# DBBC7205S.net
KiCad netlist of a schematic drawn in Altium Designer
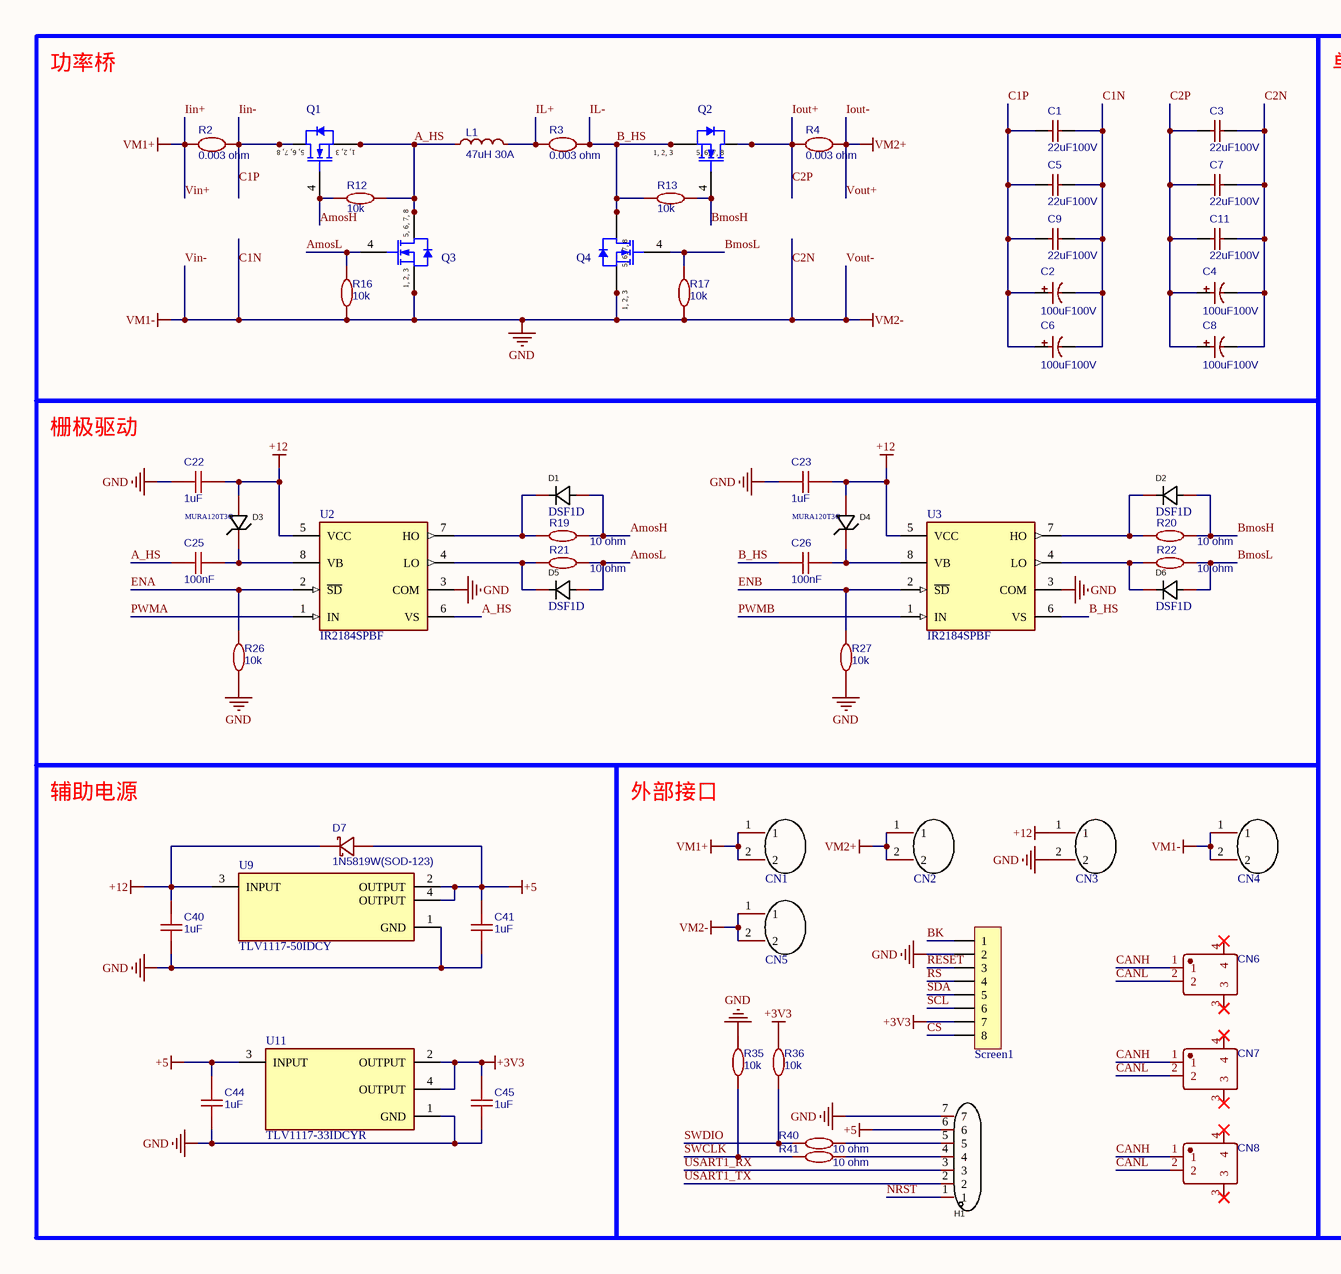
[diagram p0: DBBC7205S.SchDoc, left]
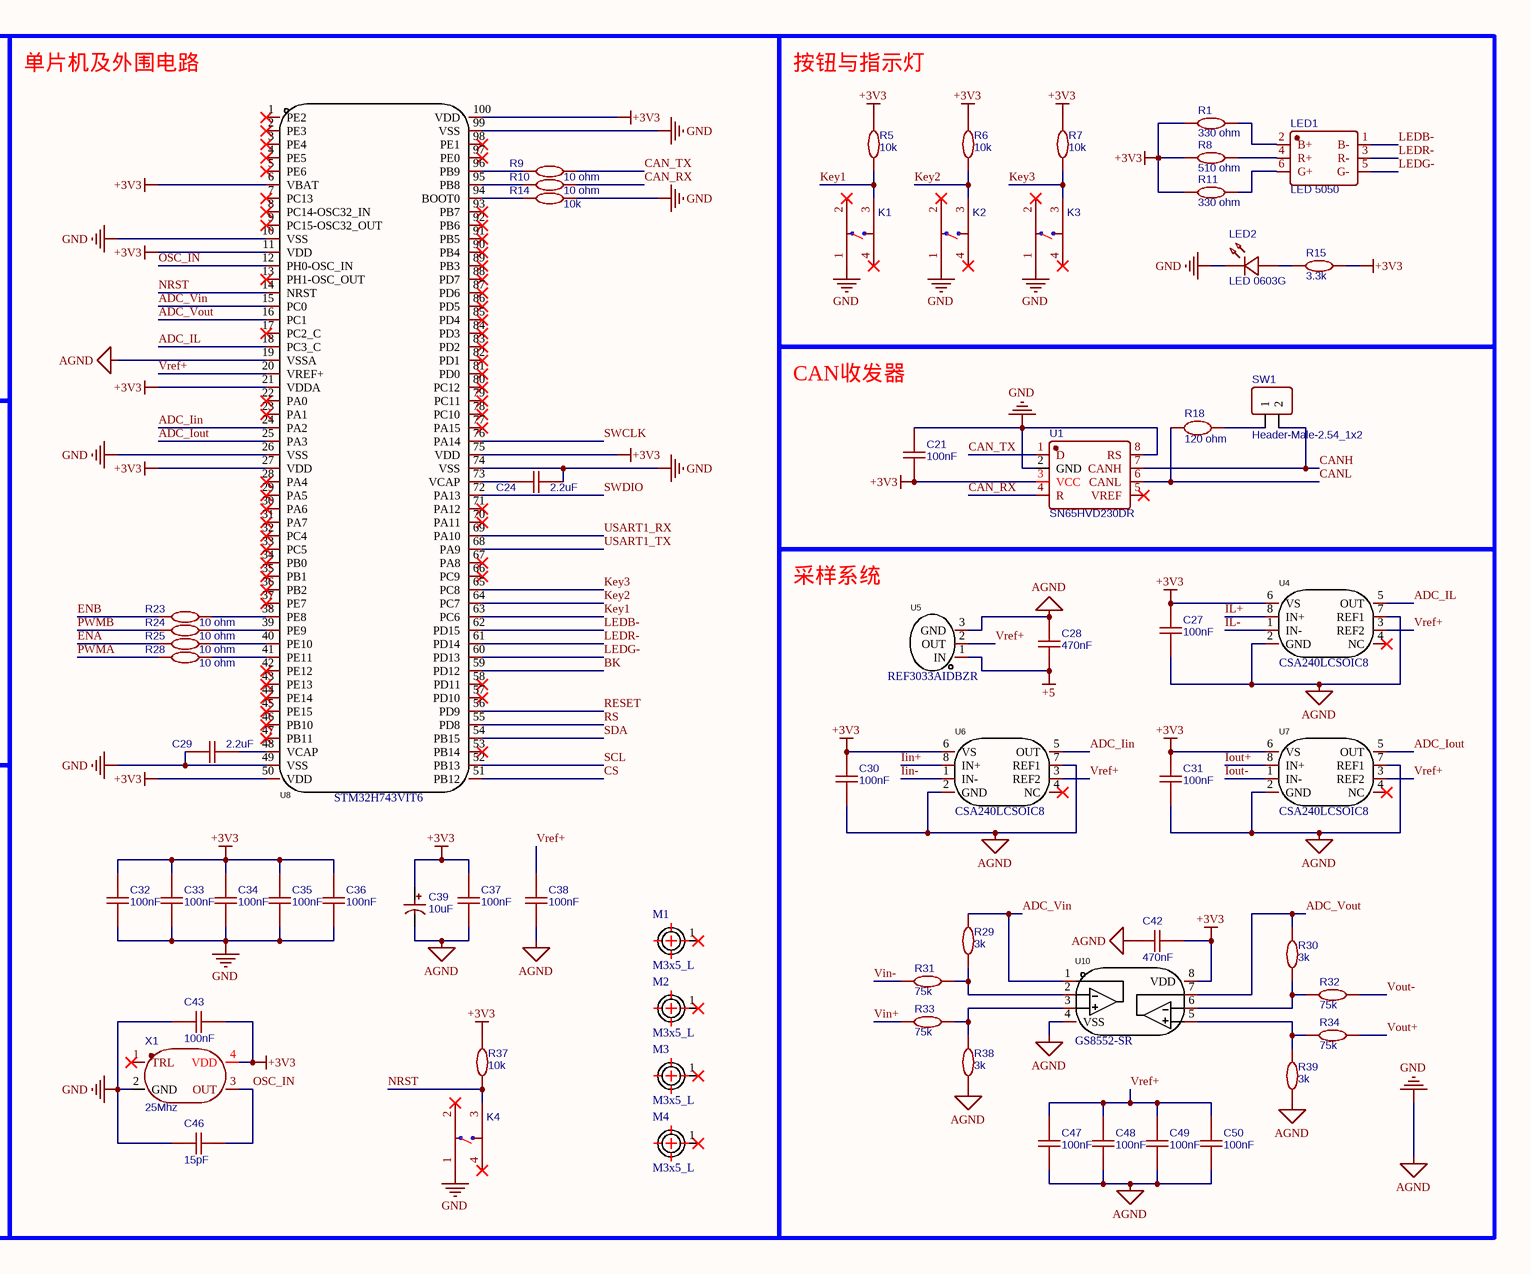
[diagram p1: DBBC7205S.SchDoc, right]

(export (version "E")
  (design (tool "Eeschema 10.0.6"))
  (components
    (comp (ref "C1")
      (value "22uF100V")
      (footprint "C1206")
      (fields
        (field (name "BOM_MANUFACTURER PART") "1206B102K202NT")
        (field (name "BOM_SUPPLIER PART") "C9196")
      )
      (libsource (lib "RC_schlib") (part "C1206"))
    )
    (comp (ref "C2")
      (value "100uF100V")
      (footprint "CAP 5.0*10*16")
      (description "脚距5mm直径10mm高度16mm")
      (fields
        (field (name "BOM_MANUFACTURER PART") "50V 100uF 8X12")
        (field (name "BOM_SUPPLIER PART") "C2749")
      )
      (libsource (lib "eCap_schlib") (part "CAP 5.0*10*16"))
    )
    (comp (ref "C3")
      (value "22uF100V")
      (footprint "C1206")
      (fields
        (field (name "BOM_MANUFACTURER PART") "1206B102K202NT")
        (field (name "BOM_SUPPLIER PART") "C9196")
      )
      (libsource (lib "RC_schlib") (part "C1206"))
    )
    (comp (ref "C4")
      (value "100uF100V")
      (footprint "CAP 5.0*10*16")
      (description "脚距5mm直径10mm高度16mm")
      (fields
        (field (name "BOM_MANUFACTURER PART") "50V 100uF 8X12")
        (field (name "BOM_SUPPLIER PART") "C2749")
      )
      (libsource (lib "eCap_schlib") (part "CAP 5.0*10*16"))
    )
    (comp (ref "C5")
      (value "22uF100V")
      (footprint "C1206")
      (fields
        (field (name "BOM_MANUFACTURER PART") "1206B102K202NT")
        (field (name "BOM_SUPPLIER PART") "C9196")
      )
      (libsource (lib "RC_schlib") (part "C1206"))
    )
    (comp (ref "C6")
      (value "100uF100V")
      (footprint "CAP 5.0*10*16")
      (description "脚距5mm直径10mm高度16mm")
      (fields
        (field (name "BOM_MANUFACTURER PART") "50V 100uF 8X12")
        (field (name "BOM_SUPPLIER PART") "C2749")
      )
      (libsource (lib "eCap_schlib") (part "CAP 5.0*10*16"))
    )
    (comp (ref "C7")
      (value "22uF100V")
      (footprint "C1206")
      (fields
        (field (name "BOM_MANUFACTURER PART") "1206B102K202NT")
        (field (name "BOM_SUPPLIER PART") "C9196")
      )
      (libsource (lib "RC_schlib") (part "C1206"))
    )
    (comp (ref "C8")
      (value "100uF100V")
      (footprint "CAP 5.0*10*16")
      (description "脚距5mm直径10mm高度16mm")
      (fields
        (field (name "BOM_MANUFACTURER PART") "50V 100uF 8X12")
        (field (name "BOM_SUPPLIER PART") "C2749")
      )
      (libsource (lib "eCap_schlib") (part "CAP 5.0*10*16"))
    )
    (comp (ref "C9")
      (value "22uF100V")
      (footprint "C1206")
      (fields
        (field (name "BOM_MANUFACTURER PART") "1206B102K202NT")
        (field (name "BOM_SUPPLIER PART") "C9196")
      )
      (libsource (lib "RC_schlib") (part "C1206"))
    )
    (comp (ref "C11")
      (value "22uF100V")
      (footprint "C1206")
      (fields
        (field (name "BOM_MANUFACTURER PART") "1206B102K202NT")
        (field (name "BOM_SUPPLIER PART") "C9196")
      )
      (libsource (lib "RC_schlib") (part "C1206"))
    )
    (comp (ref "C21")
      (value "100nF")
      (footprint "C0603")
      (fields
        (field (name "BOM_MANUFACTURER PART") "CC0603KRX7R9BB104")
        (field (name "BOM_SUPPLIER PART") "C14663")
      )
      (libsource (lib "RC_schlib") (part "C0603"))
    )
    (comp (ref "C22")
      (value "1uF")
      (footprint "C0603")
      (fields
        (field (name "BOM_MANUFACTURER PART") "CC0603KRX7R9BB104")
        (field (name "BOM_SUPPLIER PART") "C14663")
      )
      (libsource (lib "RC_schlib") (part "C0603"))
    )
    (comp (ref "C23")
      (value "1uF")
      (footprint "C0603")
      (fields
        (field (name "BOM_MANUFACTURER PART") "CC0603KRX7R9BB104")
        (field (name "BOM_SUPPLIER PART") "C14663")
      )
      (libsource (lib "RC_schlib") (part "C0603"))
    )
    (comp (ref "C24")
      (value "2.2uF")
      (footprint "C0603")
      (fields
        (field (name "BOM_MANUFACTURER PART") "CC0603KRX7R9BB104")
        (field (name "BOM_SUPPLIER PART") "C14663")
      )
      (libsource (lib "RC_schlib") (part "C0603"))
    )
    (comp (ref "C25")
      (value "100nF")
      (footprint "C0603")
      (fields
        (field (name "BOM_MANUFACTURER PART") "CC0603KRX7R9BB104")
        (field (name "BOM_SUPPLIER PART") "C14663")
      )
      (libsource (lib "RC_schlib") (part "C0603"))
    )
    (comp (ref "C26")
      (value "100nF")
      (footprint "C0603")
      (fields
        (field (name "BOM_MANUFACTURER PART") "CC0603KRX7R9BB104")
        (field (name "BOM_SUPPLIER PART") "C14663")
      )
      (libsource (lib "RC_schlib") (part "C0603"))
    )
    (comp (ref "C27")
      (value "100nF")
      (footprint "C0603")
      (fields
        (field (name "BOM_MANUFACTURER PART") "CC0603KRX7R9BB104")
        (field (name "BOM_SUPPLIER PART") "C14663")
      )
      (libsource (lib "RC_schlib") (part "C0603"))
    )
    (comp (ref "C28")
      (value "470nF")
      (footprint "C0603")
      (fields
        (field (name "BOM_MANUFACTURER PART") "CC0603KRX7R9BB104")
        (field (name "BOM_SUPPLIER PART") "C14663")
      )
      (libsource (lib "RC_schlib") (part "C0603"))
    )
    (comp (ref "C29")
      (value "2.2uF")
      (footprint "C0603")
      (fields
        (field (name "BOM_MANUFACTURER PART") "CC0603KRX7R9BB104")
        (field (name "BOM_SUPPLIER PART") "C14663")
      )
      (libsource (lib "RC_schlib") (part "C0603"))
    )
    (comp (ref "C30")
      (value "100nF")
      (footprint "C0603")
      (fields
        (field (name "BOM_MANUFACTURER PART") "CC0603KRX7R9BB104")
        (field (name "BOM_SUPPLIER PART") "C14663")
      )
      (libsource (lib "RC_schlib") (part "C0603"))
    )
    (comp (ref "C31")
      (value "100nF")
      (footprint "C0603")
      (fields
        (field (name "BOM_MANUFACTURER PART") "CC0603KRX7R9BB104")
        (field (name "BOM_SUPPLIER PART") "C14663")
      )
      (libsource (lib "RC_schlib") (part "C0603"))
    )
    (comp (ref "C32")
      (value "100nF")
      (footprint "C0603")
      (fields
        (field (name "BOM_MANUFACTURER PART") "CC0603KRX7R9BB104")
        (field (name "BOM_SUPPLIER PART") "C14663")
      )
      (libsource (lib "RC_schlib") (part "C0603"))
    )
    (comp (ref "C33")
      (value "100nF")
      (footprint "C0603")
      (fields
        (field (name "BOM_MANUFACTURER PART") "CC0603KRX7R9BB104")
        (field (name "BOM_SUPPLIER PART") "C14663")
      )
      (libsource (lib "RC_schlib") (part "C0603"))
    )
    (comp (ref "C34")
      (value "100nF")
      (footprint "C0603")
      (fields
        (field (name "BOM_MANUFACTURER PART") "CC0603KRX7R9BB104")
        (field (name "BOM_SUPPLIER PART") "C14663")
      )
      (libsource (lib "RC_schlib") (part "C0603"))
    )
    (comp (ref "C35")
      (value "100nF")
      (footprint "C0603")
      (fields
        (field (name "BOM_MANUFACTURER PART") "CC0603KRX7R9BB104")
        (field (name "BOM_SUPPLIER PART") "C14663")
      )
      (libsource (lib "RC_schlib") (part "C0603"))
    )
    (comp (ref "C36")
      (value "100nF")
      (footprint "C0603")
      (fields
        (field (name "BOM_MANUFACTURER PART") "CC0603KRX7R9BB104")
        (field (name "BOM_SUPPLIER PART") "C14663")
      )
      (libsource (lib "RC_schlib") (part "C0603"))
    )
    (comp (ref "C37")
      (value "100nF")
      (footprint "C0603")
      (fields
        (field (name "BOM_MANUFACTURER PART") "CC0603KRX7R9BB104")
        (field (name "BOM_SUPPLIER PART") "C14663")
      )
      (libsource (lib "RC_schlib") (part "C0603"))
    )
    (comp (ref "C38")
      (value "100nF")
      (footprint "C0603")
      (fields
        (field (name "BOM_MANUFACTURER PART") "CC0603KRX7R9BB104")
        (field (name "BOM_SUPPLIER PART") "C14663")
      )
      (libsource (lib "RC_schlib") (part "C0603"))
    )
    (comp (ref "C39")
      (value "10uF")
      (footprint "CD A(3216)")
      (description "长3.2mm，宽1.6mm，厚1.6mm")
      (fields
        (field (name "BOM_MANUFACTURER PART") "50V 100uF 8X12")
        (field (name "BOM_SUPPLIER PART") "C2749")
      )
      (libsource (lib "eCap_schlib") (part "A型钽电容"))
    )
    (comp (ref "C40")
      (value "1uF")
      (footprint "C0603")
      (fields
        (field (name "BOM_MANUFACTURER PART") "CC0603KRX7R9BB104")
        (field (name "BOM_SUPPLIER PART") "C14663")
      )
      (libsource (lib "RC_schlib") (part "C0603"))
    )
    (comp (ref "C41")
      (value "1uF")
      (footprint "C0603")
      (fields
        (field (name "BOM_MANUFACTURER PART") "CC0603KRX7R9BB104")
        (field (name "BOM_SUPPLIER PART") "C14663")
      )
      (libsource (lib "RC_schlib") (part "C0603"))
    )
    (comp (ref "C42")
      (value "470nF")
      (footprint "C0603")
      (fields
        (field (name "BOM_MANUFACTURER PART") "CC0603KRX7R9BB104")
        (field (name "BOM_SUPPLIER PART") "C14663")
      )
      (libsource (lib "RC_schlib") (part "C0603"))
    )
    (comp (ref "C43")
      (value "100nF")
      (footprint "C0603")
      (fields
        (field (name "BOM_MANUFACTURER PART") "CC0603KRX7R9BB104")
        (field (name "BOM_SUPPLIER PART") "C14663")
      )
      (libsource (lib "RC_schlib") (part "C0603"))
    )
    (comp (ref "C44")
      (value "1uF")
      (footprint "C0603")
      (fields
        (field (name "BOM_MANUFACTURER PART") "CC0603KRX7R9BB104")
        (field (name "BOM_SUPPLIER PART") "C14663")
      )
      (libsource (lib "RC_schlib") (part "C0603"))
    )
    (comp (ref "C45")
      (value "1uF")
      (footprint "C0603")
      (fields
        (field (name "BOM_MANUFACTURER PART") "CC0603KRX7R9BB104")
        (field (name "BOM_SUPPLIER PART") "C14663")
      )
      (libsource (lib "RC_schlib") (part "C0603"))
    )
    (comp (ref "C46")
      (value "15pF")
      (footprint "C0603")
      (fields
        (field (name "BOM_MANUFACTURER PART") "CC0603KRX7R9BB104")
        (field (name "BOM_SUPPLIER PART") "C14663")
      )
      (libsource (lib "RC_schlib") (part "C0603"))
    )
    (comp (ref "C47")
      (value "100nF")
      (footprint "C0603")
      (fields
        (field (name "BOM_MANUFACTURER PART") "CC0603KRX7R9BB104")
        (field (name "BOM_SUPPLIER PART") "C14663")
      )
      (libsource (lib "RC_schlib") (part "C0603"))
    )
    (comp (ref "C48")
      (value "100nF")
      (footprint "C0603")
      (fields
        (field (name "BOM_MANUFACTURER PART") "CC0603KRX7R9BB104")
        (field (name "BOM_SUPPLIER PART") "C14663")
      )
      (libsource (lib "RC_schlib") (part "C0603"))
    )
    (comp (ref "C49")
      (value "100nF")
      (footprint "C0603")
      (fields
        (field (name "BOM_MANUFACTURER PART") "CC0603KRX7R9BB104")
        (field (name "BOM_SUPPLIER PART") "C14663")
      )
      (libsource (lib "RC_schlib") (part "C0603"))
    )
    (comp (ref "C50")
      (value "100nF")
      (footprint "C0603")
      (fields
        (field (name "BOM_MANUFACTURER PART") "CC0603KRX7R9BB104")
        (field (name "BOM_SUPPLIER PART") "C14663")
      )
      (libsource (lib "RC_schlib") (part "C0603"))
    )
    (comp (ref "CN1")
      (value "1729128")
      (footprint "CONN-TH_2P-P5.08")
      (description "间距:5.08mm;排数:1;每排PIN数:2;安装方式:直针;额定电流:13.5A;额定电压:400V;工作温度范围:-;颜色:绿色;")
      (fields (field (name "MANUFACTURER") "Phoenix Contact(菲尼克斯)"))
      (libsource (lib "MKDSN") (part "MKDSN5.08-2P"))
    )
    (comp (ref "CN2")
      (value "1729128")
      (footprint "CONN-TH_2P-P5.08")
      (description "间距:5.08mm;排数:1;每排PIN数:2;安装方式:直针;额定电流:13.5A;额定电压:400V;工作温度范围:-;颜色:绿色;")
      (fields (field (name "MANUFACTURER") "Phoenix Contact(菲尼克斯)"))
      (libsource (lib "MKDSN") (part "MKDSN5.08-2P"))
    )
    (comp (ref "CN3")
      (value "1729128")
      (footprint "CONN-TH_2P-P5.08")
      (description "间距:5.08mm;排数:1;每排PIN数:2;安装方式:直针;额定电流:13.5A;额定电压:400V;工作温度范围:-;颜色:绿色;")
      (fields (field (name "MANUFACTURER") "Phoenix Contact(菲尼克斯)"))
      (libsource (lib "MKDSN") (part "MKDSN5.08-2P"))
    )
    (comp (ref "CN4")
      (value "1729128")
      (footprint "CONN-TH_2P-P5.08")
      (description "间距:5.08mm;排数:1;每排PIN数:2;安装方式:直针;额定电流:13.5A;额定电压:400V;工作温度范围:-;颜色:绿色;")
      (fields (field (name "MANUFACTURER") "Phoenix Contact(菲尼克斯)"))
      (libsource (lib "MKDSN") (part "MKDSN5.08-2P"))
    )
    (comp (ref "CN5")
      (value "1729128")
      (footprint "CONN-TH_2P-P5.08")
      (description "间距:5.08mm;排数:1;每排PIN数:2;安装方式:直针;额定电流:13.5A;额定电压:400V;工作温度范围:-;颜色:绿色;")
      (fields (field (name "MANUFACTURER") "Phoenix Contact(菲尼克斯)"))
      (libsource (lib "MKDSN") (part "MKDSN5.08-2P"))
    )
    (comp (ref "CN6")
      (value "A1257WR-S-2P")
      (footprint "CONN-SMD_A1257WR-S-2P")
      (fields
        (field (name "BOM_SUPPLIER PART") "C225118")
        (field (name "BOM_MANUFACTURER PART") "A1257WV-S-2P")
        (field (name "CONTRIBUTOR") "LCSC")
      )
      (libsource (lib "GH1.25_schlib") (part "A1257WR-S-2P"))
    )
    (comp (ref "CN7")
      (value "A1257WR-S-2P")
      (footprint "CONN-SMD_A1257WR-S-2P")
      (fields
        (field (name "BOM_SUPPLIER PART") "C225118")
        (field (name "BOM_MANUFACTURER PART") "A1257WV-S-2P")
        (field (name "CONTRIBUTOR") "LCSC")
      )
      (libsource (lib "GH1.25_schlib") (part "A1257WR-S-2P"))
    )
    (comp (ref "CN8")
      (value "A1257WR-S-2P")
      (footprint "CONN-SMD_A1257WR-S-2P")
      (fields
        (field (name "BOM_SUPPLIER PART") "C225118")
        (field (name "BOM_MANUFACTURER PART") "A1257WV-S-2P")
        (field (name "CONTRIBUTOR") "LCSC")
      )
      (libsource (lib "GH1.25_schlib") (part "A1257WR-S-2P"))
    )
    (comp (ref "D1")
      (value "DSF1D")
      (footprint "SOD-123_L2.8-W1.8-LS3.7-RD")
      (description "小封装快恢复二极管")
      (fields (field (name "MANUFACTURER") "FUXINSEMI(富芯森美)"))
      (libsource (lib "Diode_schlib") (part "DSF1D"))
    )
    (comp (ref "D2")
      (value "DSF1D")
      (footprint "SOD-123_L2.8-W1.8-LS3.7-RD")
      (description "小封装快恢复二极管")
      (fields (field (name "MANUFACTURER") "FUXINSEMI(富芯森美)"))
      (libsource (lib "Diode_schlib") (part "DSF1D"))
    )
    (comp (ref "D3")
      (value "MURA120T3G")
      (footprint "SMA")
      (description "25ns 0.875V压降 1A快恢复二极管")
      (fields (field (name "MANUFACTURER") "MDD") (field (name "MANUFACTURER PART") "ES1J"))
      (libsource (lib "Diode_schlib") (part "MURA120T3G"))
    )
    (comp (ref "D4")
      (value "MURA120T3G")
      (footprint "SMA")
      (description "25ns 0.875V压降 1A快恢复二极管")
      (fields (field (name "MANUFACTURER") "MDD") (field (name "MANUFACTURER PART") "ES1J"))
      (libsource (lib "Diode_schlib") (part "MURA120T3G"))
    )
    (comp (ref "D5")
      (value "DSF1D")
      (footprint "SOD-123_L2.8-W1.8-LS3.7-RD")
      (description "小封装快恢复二极管")
      (fields (field (name "MANUFACTURER") "FUXINSEMI(富芯森美)"))
      (libsource (lib "Diode_schlib") (part "DSF1D"))
    )
    (comp (ref "D6")
      (value "DSF1D")
      (footprint "SOD-123_L2.8-W1.8-LS3.7-RD")
      (description "小封装快恢复二极管")
      (fields (field (name "MANUFACTURER") "FUXINSEMI(富芯森美)"))
      (libsource (lib "Diode_schlib") (part "DSF1D"))
    )
    (comp (ref "D7")
      (value "1N5819W(SOD-123)")
      (footprint "SOD-123")
      (fields
        (field (name "BOM_SUPPLIER PART") "C2931787")
        (field (name "BOM_MANUFACTURER PART") "SS34")
        (field (name "CONTRIBUTOR") "LCSC")
      )
      (libsource (lib "Diode_schlib") (part "1N5819W(SOD-123)"))
    )
    (comp (ref "H1")
      (value "7P卧贴排母")
      (footprint "HDR-SMD_7P-P2.54-H-F-L11.5")
      (fields
        (field (name "MANUFACTURER") "XKB Connectivity(中国星坤)")
        (field (name "MANUFACTURER PART") "X6511FRS-07-C85D30")
      )
      (libsource (lib "2.54CN_schlib") (part "7P卧贴排母"))
    )
    (comp (ref "K1")
      (value "TSW SMD-6*6*5")
      (footprint "TSW SMD-6*6*5")
      (fields
        (field (name "BOM_SUPPLIER PART") "C231715")
        (field (name "BOM_MANUFACTURER PART") "KAN0661-1001B")
        (field (name "CONTRIBUTOR") "LCSC")
      )
      (libsource (lib "Button_schlib") (part "TSW SMD-6*6*5"))
    )
    (comp (ref "K2")
      (value "TSW SMD-6*6*5")
      (footprint "TSW SMD-6*6*5")
      (fields
        (field (name "BOM_SUPPLIER PART") "C231715")
        (field (name "BOM_MANUFACTURER PART") "KAN0661-1001B")
        (field (name "CONTRIBUTOR") "LCSC")
      )
      (libsource (lib "Button_schlib") (part "TSW SMD-6*6*5"))
    )
    (comp (ref "K3")
      (value "TSW SMD-6*6*5")
      (footprint "TSW SMD-6*6*5")
      (fields
        (field (name "BOM_SUPPLIER PART") "C231715")
        (field (name "BOM_MANUFACTURER PART") "KAN0661-1001B")
        (field (name "CONTRIBUTOR") "LCSC")
      )
      (libsource (lib "Button_schlib") (part "TSW SMD-6*6*5"))
    )
    (comp (ref "K4")
      (value "TSW SMD-6*6*5")
      (footprint "TSW SMD-6*6*5")
      (fields
        (field (name "BOM_SUPPLIER PART") "C231715")
        (field (name "BOM_MANUFACTURER PART") "KAN0661-1001B")
        (field (name "CONTRIBUTOR") "LCSC")
      )
      (libsource (lib "Button_schlib") (part "TSW SMD-6*6*5"))
    )
    (comp (ref "L1")
      (value "47uH 30A")
      (footprint "106-125卧式")
      (fields
        (field (name "BOM_SUPPLIER PART") "C2936653")
        (field (name "BOM_MANUFACTURER PART") "HA42-4R7MT")
        (field (name "CONTRIBUTOR") "LCSC")
      )
      (libsource (lib "Inductance_schlib") (part "106-125铁硅铝磁环电感"))
    )
    (comp (ref "LED1")
      (value "LED 5050")
      (footprint "LED 5050")
      (description "5050RGB-LED")
      (fields
        (field (name "BOM_SUPPLIER PART") "C3014404")
        (field (name "BOM_MANUFACTURER PART") "11-21/BHC-AQ2S2/2T")
        (field (name "CONTRIBUTOR") "lcsc")
      )
      (libsource (lib "LED_schlib") (part "LED 5050"))
    )
    (comp (ref "LED2")
      (value "LED 0603G")
      (footprint "LED 0603G")
      (description "绿色0603LED")
      (fields
        (field (name "BOM_SUPPLIER PART") "C3014404")
        (field (name "BOM_MANUFACTURER PART") "11-21/BHC-AQ2S2/2T")
        (field (name "CONTRIBUTOR") "lcsc")
      )
      (libsource (lib "LED_schlib") (part "LED 0603G"))
    )
    (comp (ref "M1")
      (value "M3x5_L")
      (footprint "M3x5_L")
      (description "M3铜柱，长：5mm")
      (libsource (lib "M3-CopperPillar_schlib") (part "M3x5_L"))
    )
    (comp (ref "M2")
      (value "M3x5_L")
      (footprint "M3x5_L")
      (description "M3铜柱，长：5mm")
      (libsource (lib "M3-CopperPillar_schlib") (part "M3x5_L"))
    )
    (comp (ref "M3")
      (value "M3x5_L")
      (footprint "M3x5_L")
      (description "M3铜柱，长：5mm")
      (libsource (lib "M3-CopperPillar_schlib") (part "M3x5_L"))
    )
    (comp (ref "M4")
      (value "M3x5_L")
      (footprint "M3x5_L")
      (description "M3铜柱，长：5mm")
      (libsource (lib "M3-CopperPillar_schlib") (part "M3x5_L"))
    )
    (comp (ref "Q1")
      (value "BSC070N10NS3 G")
      (footprint "INF-PG-TDSON-8-1_V")
      (fields
        (field (name "MANUFACTURER") "Infineon")
        (field (name "MANUFACTURER PART NUMBER") "BSC070N10NS3G")
      )
      (libsource (lib "MOSFET_schlib") (part "BSC070N10NS3G"))
    )
    (comp (ref "Q2")
      (value "BSC070N10NS3 G")
      (footprint "INF-PG-TDSON-8-1_V")
      (fields
        (field (name "MANUFACTURER") "Infineon")
        (field (name "MANUFACTURER PART NUMBER") "BSC070N10NS3G")
      )
      (libsource (lib "MOSFET_schlib") (part "BSC070N10NS3G"))
    )
    (comp (ref "Q3")
      (value "BSC070N10NS3 G")
      (footprint "INF-PG-TDSON-8-1_V")
      (fields
        (field (name "MANUFACTURER") "Infineon")
        (field (name "MANUFACTURER PART NUMBER") "BSC070N10NS3G")
      )
      (libsource (lib "MOSFET_schlib") (part "BSC070N10NS3G"))
    )
    (comp (ref "Q4")
      (value "BSC070N10NS3 G")
      (footprint "INF-PG-TDSON-8-1_V")
      (fields
        (field (name "MANUFACTURER") "Infineon")
        (field (name "MANUFACTURER PART NUMBER") "BSC070N10NS3G")
      )
      (libsource (lib "MOSFET_schlib") (part "BSC070N10NS3G"))
    )
    (comp (ref "R1")
      (value "330 ohm")
      (footprint "R0603")
      (fields
        (field (name "BOM_SUPPLIER PART") "C326890")
        (field (name "BOM_MANUFACTURER PART") "SR0603JR-071RL")
        (field (name "CONTRIBUTOR") "LCSC")
      )
      (libsource (lib "RC_schlib") (part "R0603"))
    )
    (comp (ref "R2")
      (value "0.003 ohm")
      (footprint "R2512")
      (fields
        (field (name "BOM_SUPPLIER PART") "C375694")
        (field (name "BOM_MANUFACTURER PART") "SR2512FK-0751RL")
        (field (name "CONTRIBUTOR") "LCSC")
      )
      (libsource (lib "RC_schlib") (part "R2512"))
    )
    (comp (ref "R3")
      (value "0.003 ohm")
      (footprint "R2512")
      (fields
        (field (name "BOM_SUPPLIER PART") "C375694")
        (field (name "BOM_MANUFACTURER PART") "SR2512FK-0751RL")
        (field (name "CONTRIBUTOR") "LCSC")
      )
      (libsource (lib "RC_schlib") (part "R2512"))
    )
    (comp (ref "R4")
      (value "0.003 ohm")
      (footprint "R2512")
      (fields
        (field (name "BOM_SUPPLIER PART") "C375694")
        (field (name "BOM_MANUFACTURER PART") "SR2512FK-0751RL")
        (field (name "CONTRIBUTOR") "LCSC")
      )
      (libsource (lib "RC_schlib") (part "R2512"))
    )
    (comp (ref "R5")
      (value "10k")
      (footprint "R0603")
      (fields
        (field (name "BOM_SUPPLIER PART") "C326890")
        (field (name "BOM_MANUFACTURER PART") "SR0603JR-071RL")
        (field (name "CONTRIBUTOR") "LCSC")
      )
      (libsource (lib "RC_schlib") (part "R0603"))
    )
    (comp (ref "R6")
      (value "10k")
      (footprint "R0603")
      (fields
        (field (name "BOM_SUPPLIER PART") "C326890")
        (field (name "BOM_MANUFACTURER PART") "SR0603JR-071RL")
        (field (name "CONTRIBUTOR") "LCSC")
      )
      (libsource (lib "RC_schlib") (part "R0603"))
    )
    (comp (ref "R7")
      (value "10k")
      (footprint "R0603")
      (fields
        (field (name "BOM_SUPPLIER PART") "C326890")
        (field (name "BOM_MANUFACTURER PART") "SR0603JR-071RL")
        (field (name "CONTRIBUTOR") "LCSC")
      )
      (libsource (lib "RC_schlib") (part "R0603"))
    )
    (comp (ref "R8")
      (value "510 ohm")
      (footprint "R0603")
      (fields
        (field (name "BOM_SUPPLIER PART") "C326890")
        (field (name "BOM_MANUFACTURER PART") "SR0603JR-071RL")
        (field (name "CONTRIBUTOR") "LCSC")
      )
      (libsource (lib "RC_schlib") (part "R0603"))
    )
    (comp (ref "R9")
      (value "10 ohm")
      (footprint "R0603")
      (fields
        (field (name "BOM_SUPPLIER PART") "C326890")
        (field (name "BOM_MANUFACTURER PART") "SR0603JR-071RL")
        (field (name "CONTRIBUTOR") "LCSC")
      )
      (libsource (lib "RC_schlib") (part "R0603"))
    )
    (comp (ref "R10")
      (value "10 ohm")
      (footprint "R0603")
      (fields
        (field (name "BOM_SUPPLIER PART") "C326890")
        (field (name "BOM_MANUFACTURER PART") "SR0603JR-071RL")
        (field (name "CONTRIBUTOR") "LCSC")
      )
      (libsource (lib "RC_schlib") (part "R0603"))
    )
    (comp (ref "R11")
      (value "330 ohm")
      (footprint "R0603")
      (fields
        (field (name "BOM_SUPPLIER PART") "C326890")
        (field (name "BOM_MANUFACTURER PART") "SR0603JR-071RL")
        (field (name "CONTRIBUTOR") "LCSC")
      )
      (libsource (lib "RC_schlib") (part "R0603"))
    )
    (comp (ref "R12")
      (value "10k")
      (footprint "R0603")
      (fields
        (field (name "BOM_SUPPLIER PART") "C326890")
        (field (name "BOM_MANUFACTURER PART") "SR0603JR-071RL")
        (field (name "CONTRIBUTOR") "LCSC")
      )
      (libsource (lib "RC_schlib") (part "R0603"))
    )
    (comp (ref "R13")
      (value "10k")
      (footprint "R0603")
      (fields
        (field (name "BOM_SUPPLIER PART") "C326890")
        (field (name "BOM_MANUFACTURER PART") "SR0603JR-071RL")
        (field (name "CONTRIBUTOR") "LCSC")
      )
      (libsource (lib "RC_schlib") (part "R0603"))
    )
    (comp (ref "R14")
      (value "10k")
      (footprint "R0603")
      (fields
        (field (name "BOM_SUPPLIER PART") "C326890")
        (field (name "BOM_MANUFACTURER PART") "SR0603JR-071RL")
        (field (name "CONTRIBUTOR") "LCSC")
      )
      (libsource (lib "RC_schlib") (part "R0603"))
    )
    (comp (ref "R15")
      (value "3.3k")
      (footprint "R0603")
      (fields
        (field (name "BOM_SUPPLIER PART") "C326890")
        (field (name "BOM_MANUFACTURER PART") "SR0603JR-071RL")
        (field (name "CONTRIBUTOR") "LCSC")
      )
      (libsource (lib "RC_schlib") (part "R0603"))
    )
    (comp (ref "R16")
      (value "10k")
      (footprint "R0603")
      (fields
        (field (name "BOM_SUPPLIER PART") "C326890")
        (field (name "BOM_MANUFACTURER PART") "SR0603JR-071RL")
        (field (name "CONTRIBUTOR") "LCSC")
      )
      (libsource (lib "RC_schlib") (part "R0603"))
    )
    (comp (ref "R17")
      (value "10k")
      (footprint "R0603")
      (fields
        (field (name "BOM_SUPPLIER PART") "C326890")
        (field (name "BOM_MANUFACTURER PART") "SR0603JR-071RL")
        (field (name "CONTRIBUTOR") "LCSC")
      )
      (libsource (lib "RC_schlib") (part "R0603"))
    )
    (comp (ref "R18")
      (value "120 ohm")
      (footprint "R0805")
      (fields
        (field (name "BOM_SUPPLIER PART") "C723409")
        (field (name "BOM_MANUFACTURER PART") "SR0805FR-0710RL")
        (field (name "CONTRIBUTOR") "LCSC")
      )
      (libsource (lib "RC_schlib") (part "R0805"))
    )
    (comp (ref "R19")
      (value "10 ohm")
      (footprint "R0603")
      (fields
        (field (name "BOM_SUPPLIER PART") "C326890")
        (field (name "BOM_MANUFACTURER PART") "SR0603JR-071RL")
        (field (name "CONTRIBUTOR") "LCSC")
      )
      (libsource (lib "RC_schlib") (part "R0603"))
    )
    (comp (ref "R20")
      (value "10 ohm")
      (footprint "R0603")
      (fields
        (field (name "BOM_SUPPLIER PART") "C326890")
        (field (name "BOM_MANUFACTURER PART") "SR0603JR-071RL")
        (field (name "CONTRIBUTOR") "LCSC")
      )
      (libsource (lib "RC_schlib") (part "R0603"))
    )
    (comp (ref "R21")
      (value "10 ohm")
      (footprint "R0603")
      (fields
        (field (name "BOM_SUPPLIER PART") "C326890")
        (field (name "BOM_MANUFACTURER PART") "SR0603JR-071RL")
        (field (name "CONTRIBUTOR") "LCSC")
      )
      (libsource (lib "RC_schlib") (part "R0603"))
    )
    (comp (ref "R22")
      (value "10 ohm")
      (footprint "R0603")
      (fields
        (field (name "BOM_SUPPLIER PART") "C326890")
        (field (name "BOM_MANUFACTURER PART") "SR0603JR-071RL")
        (field (name "CONTRIBUTOR") "LCSC")
      )
      (libsource (lib "RC_schlib") (part "R0603"))
    )
    (comp (ref "R23")
      (value "10 ohm")
      (footprint "R0603")
      (fields
        (field (name "BOM_SUPPLIER PART") "C326890")
        (field (name "BOM_MANUFACTURER PART") "SR0603JR-071RL")
        (field (name "CONTRIBUTOR") "LCSC")
      )
      (libsource (lib "RC_schlib") (part "R0603"))
    )
    (comp (ref "R24")
      (value "10 ohm")
      (footprint "R0603")
      (fields
        (field (name "BOM_SUPPLIER PART") "C326890")
        (field (name "BOM_MANUFACTURER PART") "SR0603JR-071RL")
        (field (name "CONTRIBUTOR") "LCSC")
      )
      (libsource (lib "RC_schlib") (part "R0603"))
    )
    (comp (ref "R25")
      (value "10 ohm")
      (footprint "R0603")
      (fields
        (field (name "BOM_SUPPLIER PART") "C326890")
        (field (name "BOM_MANUFACTURER PART") "SR0603JR-071RL")
        (field (name "CONTRIBUTOR") "LCSC")
      )
      (libsource (lib "RC_schlib") (part "R0603"))
    )
    (comp (ref "R26")
      (value "10k")
      (footprint "R0603")
      (fields
        (field (name "BOM_SUPPLIER PART") "C326890")
        (field (name "BOM_MANUFACTURER PART") "SR0603JR-071RL")
        (field (name "CONTRIBUTOR") "LCSC")
      )
      (libsource (lib "RC_schlib") (part "R0603"))
    )
    (comp (ref "R27")
      (value "10k")
      (footprint "R0603")
      (fields
        (field (name "BOM_SUPPLIER PART") "C326890")
        (field (name "BOM_MANUFACTURER PART") "SR0603JR-071RL")
        (field (name "CONTRIBUTOR") "LCSC")
      )
      (libsource (lib "RC_schlib") (part "R0603"))
    )
    (comp (ref "R28")
      (value "10 ohm")
      (footprint "R0603")
      (fields
        (field (name "BOM_SUPPLIER PART") "C326890")
        (field (name "BOM_MANUFACTURER PART") "SR0603JR-071RL")
        (field (name "CONTRIBUTOR") "LCSC")
      )
      (libsource (lib "RC_schlib") (part "R0603"))
    )
    (comp (ref "R29")
      (value "3k")
      (footprint "R0603")
      (fields
        (field (name "BOM_SUPPLIER PART") "C326890")
        (field (name "BOM_MANUFACTURER PART") "SR0603JR-071RL")
        (field (name "CONTRIBUTOR") "LCSC")
      )
      (libsource (lib "RC_schlib") (part "R0603"))
    )
    (comp (ref "R30")
      (value "3k")
      (footprint "R0603")
      (fields
        (field (name "BOM_SUPPLIER PART") "C326890")
        (field (name "BOM_MANUFACTURER PART") "SR0603JR-071RL")
        (field (name "CONTRIBUTOR") "LCSC")
      )
      (libsource (lib "RC_schlib") (part "R0603"))
    )
    (comp (ref "R31")
      (value "75k")
      (footprint "R0603")
      (fields
        (field (name "BOM_SUPPLIER PART") "C326890")
        (field (name "BOM_MANUFACTURER PART") "SR0603JR-071RL")
        (field (name "CONTRIBUTOR") "LCSC")
      )
      (libsource (lib "RC_schlib") (part "R0603"))
    )
    (comp (ref "R32")
      (value "75k")
      (footprint "R0603")
      (fields
        (field (name "BOM_SUPPLIER PART") "C326890")
        (field (name "BOM_MANUFACTURER PART") "SR0603JR-071RL")
        (field (name "CONTRIBUTOR") "LCSC")
      )
      (libsource (lib "RC_schlib") (part "R0603"))
    )
    (comp (ref "R33")
      (value "75k")
      (footprint "R0603")
      (fields
        (field (name "BOM_SUPPLIER PART") "C326890")
        (field (name "BOM_MANUFACTURER PART") "SR0603JR-071RL")
        (field (name "CONTRIBUTOR") "LCSC")
      )
      (libsource (lib "RC_schlib") (part "R0603"))
    )
    (comp (ref "R34")
      (value "75k")
      (footprint "R0603")
      (fields
        (field (name "BOM_SUPPLIER PART") "C326890")
        (field (name "BOM_MANUFACTURER PART") "SR0603JR-071RL")
        (field (name "CONTRIBUTOR") "LCSC")
      )
      (libsource (lib "RC_schlib") (part "R0603"))
    )
    (comp (ref "R35")
      (value "10k")
      (footprint "R0603")
      (fields
        (field (name "BOM_SUPPLIER PART") "C326890")
        (field (name "BOM_MANUFACTURER PART") "SR0603JR-071RL")
        (field (name "CONTRIBUTOR") "LCSC")
      )
      (libsource (lib "RC_schlib") (part "R0603"))
    )
    (comp (ref "R36")
      (value "10k")
      (footprint "R0603")
      (fields
        (field (name "BOM_SUPPLIER PART") "C326890")
        (field (name "BOM_MANUFACTURER PART") "SR0603JR-071RL")
        (field (name "CONTRIBUTOR") "LCSC")
      )
      (libsource (lib "RC_schlib") (part "R0603"))
    )
    (comp (ref "R37")
      (value "10k")
      (footprint "R0603")
      (fields
        (field (name "BOM_SUPPLIER PART") "C326890")
        (field (name "BOM_MANUFACTURER PART") "SR0603JR-071RL")
        (field (name "CONTRIBUTOR") "LCSC")
      )
      (libsource (lib "RC_schlib") (part "R0603"))
    )
    (comp (ref "R38")
      (value "3k")
      (footprint "R0603")
      (fields
        (field (name "BOM_SUPPLIER PART") "C326890")
        (field (name "BOM_MANUFACTURER PART") "SR0603JR-071RL")
        (field (name "CONTRIBUTOR") "LCSC")
      )
      (libsource (lib "RC_schlib") (part "R0603"))
    )
    (comp (ref "R39")
      (value "3k")
      (footprint "R0603")
      (fields
        (field (name "BOM_SUPPLIER PART") "C326890")
        (field (name "BOM_MANUFACTURER PART") "SR0603JR-071RL")
        (field (name "CONTRIBUTOR") "LCSC")
      )
      (libsource (lib "RC_schlib") (part "R0603"))
    )
    (comp (ref "R40")
      (value "10 ohm")
      (footprint "R0603")
      (fields
        (field (name "BOM_SUPPLIER PART") "C326890")
        (field (name "BOM_MANUFACTURER PART") "SR0603JR-071RL")
        (field (name "CONTRIBUTOR") "LCSC")
      )
      (libsource (lib "RC_schlib") (part "R0603"))
    )
    (comp (ref "R41")
      (value "10 ohm")
      (footprint "R0603")
      (fields
        (field (name "BOM_SUPPLIER PART") "C326890")
        (field (name "BOM_MANUFACTURER PART") "SR0603JR-071RL")
        (field (name "CONTRIBUTOR") "LCSC")
      )
      (libsource (lib "RC_schlib") (part "R0603"))
    )
    (comp (ref "Screen1")
      (value "FPC0.5-8P")
      (footprint "FPC0.5 2H-S-W-8P")
      (description "FPC连接器")
      (fields (field (name "版权归属") "黎明电子style"))
      (libsource (lib "FPC_schlib") (part "FPC-8P-0.5"))
    )
    (comp (ref "SW1")
      (value "Header-Male-2.54_1x2")
      (footprint "HDR2.54-LI-2P")
      (fields
        (field (name "BOM_MANUFACTURER PART") "Header2.54mm 1*3P")
        (field (name "BOM_SUPPLIER PART") "C49257")
      )
      (libsource (lib "2.54CN_schlib") (part "Header-Male-2.54_1x2"))
    )
    (comp (ref "U1")
      (value "SN65HVD230DR")
      (footprint "SOP-8")
      (description "常用CAN收发器")
      (fields (field (name "BOM_SUPPLIER PART") "C12084"))
      (libsource (lib "IC_schlib") (part "SN65HVD230DR"))
    )
    (comp (ref "U2")
      (value "IR2184SPBF")
      (footprint "FP-PG-DSO-8-MFG")
      (description "IC GATE DRVR HALF-BRIDGE 8SOIC")
      (fields
        (field (name "MANUFACTURER") "Infineon")
        (field (name "OCTOPART") "https://octopart.com/ir2184spbf-infineon-65872954")
      )
      (libsource (lib "Altium Content Vault") (part "eadb07069977034a324a47831dd6aaa"))
    )
    (comp (ref "U3")
      (value "IR2184SPBF")
      (footprint "FP-PG-DSO-8-MFG")
      (description "IC GATE DRVR HALF-BRIDGE 8SOIC")
      (fields
        (field (name "MANUFACTURER") "Infineon")
        (field (name "OCTOPART") "https://octopart.com/ir2184spbf-infineon-65872954")
      )
      (libsource (lib "Altium Content Vault") (part "eadb07069977034a324a47831dd6aaa"))
    )
    (comp (ref "U4")
      (value "CSA240LCSOIC8")
      (footprint "SOIC-8_L4.9-W3.9-P1.27-LS6.0-BL")
      (description "低噪声低温漂双向电流高端检测芯片")
      (fields (field (name "MANUFACTURER") "analogysemi(类比半导体)"))
      (libsource (lib "IC_schlib") (part "CSA240LCSOIC8"))
    )
    (comp (ref "U5")
      (value "REF3033AIDBZR")
      (footprint "SOT-23-3_L3.0-W1.7-P0.95-LS2.9-BR")
      (description "3.3V基准电压源")
      (fields (field (name "MANUFACTURER") "TI(德州仪器)") (field (name "TOLERANCE") "±0.2%"))
      (libsource (lib "IC_schlib") (part "REF3033AIDBZR"))
    )
    (comp (ref "U6")
      (value "CSA240LCSOIC8")
      (footprint "SOIC-8_L4.9-W3.9-P1.27-LS6.0-BL")
      (description "低噪声低温漂双向电流高端检测芯片")
      (fields (field (name "MANUFACTURER") "analogysemi(类比半导体)"))
      (libsource (lib "IC_schlib") (part "CSA240LCSOIC8"))
    )
    (comp (ref "U7")
      (value "CSA240LCSOIC8")
      (footprint "SOIC-8_L4.9-W3.9-P1.27-LS6.0-BL")
      (description "低噪声低温漂双向电流高端检测芯片")
      (fields (field (name "MANUFACTURER") "analogysemi(类比半导体)"))
      (libsource (lib "IC_schlib") (part "CSA240LCSOIC8"))
    )
    (comp (ref "U8")
      (value "STM32H743VIT6")
      (footprint "LQFP-100_L14.0-W14.0-P0.50-LS16.0-BL")
      (description "STM32H7")
      (fields (field (name "MANUFACTURER") "ST(意法半导体)"))
      (libsource (lib "IC_schlib") (part "STM32H743VIT6"))
    )
    (comp (ref "U9")
      (value "TLV1117-50IDCY")
      (footprint "FP-DCY0004A-MFG")
      (description "IC REG LINEAR 5V 800MA SOT223-4")
      (libsource (lib "Altium Content Vault") (part "e308c0431133a401381f8e374ae96fd"))
    )
    (comp (ref "U10")
      (value "GS8552-SR")
      (footprint "SOIC-8_L4.9-W3.9-P1.27-LS6.0-BL")
      (description "1.5MHZ, 轨到轨高精双通道运放")
      (fields (field (name "MANUFACTURER") "Gainsil(聚洵)"))
      (libsource (lib "IC_schlib") (part "GS8552-SR"))
    )
    (comp (ref "U11")
      (value "TLV1117-33IDCYR")
      (footprint "FP-DCY0004A-MFG")
      (description "IC REG LIN 3.3V 800MA SOT223-4")
      (fields
        (field (name "MANUFACTURER") "Texas Instruments")
        (field (name "OCTOPART") "https://octopart.com/tlv1117-33idcyr-texas+instruments-669250")
      )
      (libsource (lib "Altium Content Vault") (part "d420fb9686013fb832e66295cdf4acf"))
    )
    (comp (ref "X1")
      (value "25Mhz")
      (footprint "OSC 3225-4P")
      (fields
        (field (name "BOM_SUPPLIER PART") "C454610")
        (field (name "BOM_MANUFACTURER PART") "TFOM8M4RHKCNT2T")
        (field (name "CONTRIBUTOR") "LCSC")
      )
      (libsource (lib "OSC_schilb") (part "OSC-3225"))
    )
  )
  (nets
    (net (code "1") (name "+3V3") (class "Default")
      (node (ref "C21") (pin "1") (pinfunction "1_1") (pintype "passive"))
      (node (ref "C27") (pin "2") (pinfunction "2_2") (pintype "passive"))
      (node (ref "C30") (pin "2") (pinfunction "2_2") (pintype "passive"))
      (node (ref "C31") (pin "2") (pinfunction "2_2") (pintype "passive"))
      (node (ref "C32") (pin "2") (pinfunction "2_2") (pintype "passive"))
      (node (ref "C33") (pin "2") (pinfunction "2_2") (pintype "passive"))
      (node (ref "C34") (pin "2") (pinfunction "2_2") (pintype "passive"))
      (node (ref "C35") (pin "2") (pinfunction "2_2") (pintype "passive"))
      (node (ref "C36") (pin "2") (pinfunction "2_2") (pintype "passive"))
      (node (ref "C37") (pin "1") (pinfunction "1_1") (pintype "passive"))
      (node (ref "C39") (pin "1") (pinfunction "1_1") (pintype "passive"))
      (node (ref "C42") (pin "2") (pinfunction "2_2") (pintype "passive"))
      (node (ref "C43") (pin "2") (pinfunction "2_2") (pintype "passive"))
      (node (ref "C45") (pin "2") (pinfunction "2_2") (pintype "passive"))
      (node (ref "R1") (pin "2") (pinfunction "2_2") (pintype "passive"))
      (node (ref "R11") (pin "2") (pinfunction "2_2") (pintype "passive"))
      (node (ref "R15") (pin "1") (pinfunction "1_1") (pintype "passive"))
      (node (ref "R36") (pin "2") (pinfunction "2_2") (pintype "passive"))
      (node (ref "R37") (pin "2") (pinfunction "2_2") (pintype "passive"))
      (node (ref "R5") (pin "2") (pinfunction "2_2") (pintype "passive"))
      (node (ref "R6") (pin "2") (pinfunction "2_2") (pintype "passive"))
      (node (ref "R7") (pin "2") (pinfunction "2_2") (pintype "passive"))
      (node (ref "R8") (pin "2") (pinfunction "2_2") (pintype "passive"))
      (node (ref "Screen1") (pin "7") (pinfunction "7_7") (pintype "passive"))
      (node (ref "U1") (pin "3") (pinfunction "VCC_3") (pintype "passive"))
      (node (ref "U10") (pin "8") (pinfunction "VDD_8") (pintype "passive"))
      (node (ref "U11") (pin "2") (pinfunction "OUTPUT_2") (pintype "power_in"))
      (node (ref "U11") (pin "4") (pinfunction "OUTPUT_4") (pintype "power_in"))
      (node (ref "U4") (pin "6") (pinfunction "VS_6") (pintype "passive"))
      (node (ref "U6") (pin "6") (pinfunction "VS_6") (pintype "passive"))
      (node (ref "U7") (pin "6") (pinfunction "VS_6") (pintype "passive"))
      (node (ref "U8") (pin "100") (pinfunction "VDD_100") (pintype "passive"))
      (node (ref "U8") (pin "11") (pinfunction "VDD_11") (pintype "passive"))
      (node (ref "U8") (pin "21") (pinfunction "VDDA_21") (pintype "passive"))
      (node (ref "U8") (pin "27") (pinfunction "VDD_27") (pintype "passive"))
      (node (ref "U8") (pin "50") (pinfunction "VDD_50") (pintype "passive"))
      (node (ref "U8") (pin "6") (pinfunction "VBAT_6") (pintype "passive"))
      (node (ref "U8") (pin "75") (pinfunction "VDD_75") (pintype "passive"))
      (node (ref "X1") (pin "4") (pinfunction "VDD_4") (pintype "passive"))
    )
    (net (code "2") (name "+5") (class "Default")
      (node (ref "C28") (pin "1") (pinfunction "1_1") (pintype "passive"))
      (node (ref "C41") (pin "2") (pinfunction "2_2") (pintype "passive"))
      (node (ref "C44") (pin "2") (pinfunction "2_2") (pintype "passive"))
      (node (ref "D7") (pin "1") (pinfunction "A_1") (pintype "passive"))
      (node (ref "H1") (pin "6") (pinfunction "6_6") (pintype "passive"))
      (node (ref "U11") (pin "3") (pinfunction "INPUT_3") (pintype "power_in"))
      (node (ref "U5") (pin "1") (pinfunction "IN_1") (pintype "passive"))
      (node (ref "U9") (pin "2") (pinfunction "OUTPUT_2") (pintype "power_in"))
      (node (ref "U9") (pin "4") (pinfunction "OUTPUT_4") (pintype "power_in"))
    )
    (net (code "3") (name "+12") (class "Default")
      (node (ref "C22") (pin "2") (pinfunction "2_2") (pintype "passive"))
      (node (ref "C23") (pin "2") (pinfunction "2_2") (pintype "passive"))
      (node (ref "C40") (pin "2") (pinfunction "2_2") (pintype "passive"))
      (node (ref "CN3") (pin "1") (pinfunction "1_1") (pintype "passive"))
      (node (ref "D3") (pin "1") (pinfunction "A_1") (pintype "passive"))
      (node (ref "D4") (pin "1") (pinfunction "A_1") (pintype "passive"))
      (node (ref "D7") (pin "2") (pinfunction "K_2") (pintype "passive"))
      (node (ref "U2") (pin "5") (pinfunction "VCC_5") (pintype "power_in"))
      (node (ref "U3") (pin "5") (pinfunction "VCC_5") (pintype "power_in"))
      (node (ref "U9") (pin "3") (pinfunction "INPUT_3") (pintype "power_in"))
    )
    (net (code "4") (name "/ADC_IL") (class "Default")
      (node (ref "U4") (pin "5") (pinfunction "OUT_5") (pintype "passive"))
      (node (ref "U8") (pin "18") (pinfunction "PC3_C_18") (pintype "passive"))
    )
    (net (code "5") (name "/ADC_Iin") (class "Default")
      (node (ref "U6") (pin "5") (pinfunction "OUT_5") (pintype "passive"))
      (node (ref "U8") (pin "24") (pinfunction "PA2_24") (pintype "passive"))
    )
    (net (code "6") (name "/ADC_Iout") (class "Default")
      (node (ref "U7") (pin "5") (pinfunction "OUT_5") (pintype "passive"))
      (node (ref "U8") (pin "25") (pinfunction "PA3_25") (pintype "passive"))
    )
    (net (code "7") (name "/ADC_Vin") (class "Default")
      (node (ref "R29") (pin "2") (pinfunction "2_2") (pintype "passive"))
      (node (ref "U10") (pin "1") (pinfunction "OUTA_1") (pintype "passive"))
      (node (ref "U8") (pin "15") (pinfunction "PC0_15") (pintype "passive"))
    )
    (net (code "8") (name "/ADC_Vout") (class "Default")
      (node (ref "R30") (pin "2") (pinfunction "2_2") (pintype "passive"))
      (node (ref "U10") (pin "7") (pinfunction "OUTB_7") (pintype "passive"))
      (node (ref "U8") (pin "16") (pinfunction "PC1_16") (pintype "passive"))
    )
    (net (code "9") (name "/A_HS") (class "Default")
      (node (ref "C25") (pin "2") (pinfunction "2_2") (pintype "passive"))
      (node (ref "L1") (pin "1") (pinfunction "1_1") (pintype "passive"))
      (node (ref "Q1") (pin "1") (pinfunction "SOURCE_1") (pintype "passive"))
      (node (ref "Q1") (pin "2") (pinfunction "SOURCE_2") (pintype "passive"))
      (node (ref "Q1") (pin "3") (pinfunction "SOURCE_3") (pintype "passive"))
      (node (ref "Q3") (pin "5") (pinfunction "DRAIN_5") (pintype "passive"))
      (node (ref "Q3") (pin "6") (pinfunction "DRAIN_6") (pintype "passive"))
      (node (ref "Q3") (pin "7") (pinfunction "DRAIN_7") (pintype "passive"))
      (node (ref "Q3") (pin "8") (pinfunction "DRAIN_8") (pintype "passive"))
      (node (ref "R12") (pin "1") (pinfunction "1_1") (pintype "passive"))
      (node (ref "U2") (pin "6") (pinfunction "VS_6") (pintype "power_in"))
    )
    (net (code "10") (name "/AmosH") (class "Default")
      (node (ref "D1") (pin "2") (pinfunction "A_2") (pintype "passive"))
      (node (ref "Q1") (pin "4") (pinfunction "GATE_4") (pintype "passive"))
      (node (ref "R12") (pin "2") (pinfunction "2_2") (pintype "passive"))
      (node (ref "R19") (pin "2") (pinfunction "2_2") (pintype "passive"))
    )
    (net (code "11") (name "/AmosL") (class "Default")
      (node (ref "D5") (pin "2") (pinfunction "A_2") (pintype "passive"))
      (node (ref "Q3") (pin "4") (pinfunction "GATE_4") (pintype "passive"))
      (node (ref "R16") (pin "2") (pinfunction "2_2") (pintype "passive"))
      (node (ref "R21") (pin "2") (pinfunction "2_2") (pintype "passive"))
    )
    (net (code "12") (name "/BK") (class "Default")
      (node (ref "Screen1") (pin "1") (pinfunction "1_1") (pintype "passive"))
      (node (ref "U8") (pin "59") (pinfunction "PD12_59") (pintype "passive"))
    )
    (net (code "13") (name "/B_HS") (class "Default")
      (node (ref "C26") (pin "2") (pinfunction "2_2") (pintype "passive"))
      (node (ref "Q2") (pin "1") (pinfunction "SOURCE_1") (pintype "passive"))
      (node (ref "Q2") (pin "2") (pinfunction "SOURCE_2") (pintype "passive"))
      (node (ref "Q2") (pin "3") (pinfunction "SOURCE_3") (pintype "passive"))
      (node (ref "Q4") (pin "5") (pinfunction "DRAIN_5") (pintype "passive"))
      (node (ref "Q4") (pin "6") (pinfunction "DRAIN_6") (pintype "passive"))
      (node (ref "Q4") (pin "7") (pinfunction "DRAIN_7") (pintype "passive"))
      (node (ref "Q4") (pin "8") (pinfunction "DRAIN_8") (pintype "passive"))
      (node (ref "R13") (pin "2") (pinfunction "2_2") (pintype "passive"))
      (node (ref "R3") (pin "2") (pinfunction "2_2") (pintype "passive"))
      (node (ref "U3") (pin "6") (pinfunction "VS_6") (pintype "power_in"))
      (node (ref "U4") (pin "1") (pinfunction "IN-_1") (pintype "passive"))
    )
    (net (code "14") (name "/BmosH") (class "Default")
      (node (ref "D2") (pin "2") (pinfunction "A_2") (pintype "passive"))
      (node (ref "Q2") (pin "4") (pinfunction "GATE_4") (pintype "passive"))
      (node (ref "R13") (pin "1") (pinfunction "1_1") (pintype "passive"))
      (node (ref "R20") (pin "2") (pinfunction "2_2") (pintype "passive"))
    )
    (net (code "15") (name "/BmosL") (class "Default")
      (node (ref "D6") (pin "2") (pinfunction "A_2") (pintype "passive"))
      (node (ref "Q4") (pin "4") (pinfunction "GATE_4") (pintype "passive"))
      (node (ref "R17") (pin "2") (pinfunction "2_2") (pintype "passive"))
      (node (ref "R22") (pin "2") (pinfunction "2_2") (pintype "passive"))
    )
    (net (code "16") (name "/C1P") (class "Default")
      (node (ref "C1") (pin "1") (pinfunction "1_1") (pintype "passive"))
      (node (ref "C2") (pin "1") (pinfunction "1_1") (pintype "passive"))
      (node (ref "C5") (pin "1") (pinfunction "1_1") (pintype "passive"))
      (node (ref "C6") (pin "1") (pinfunction "1_1") (pintype "passive"))
      (node (ref "C9") (pin "1") (pinfunction "1_1") (pintype "passive"))
      (node (ref "Q1") (pin "5") (pinfunction "DRAIN_5") (pintype "passive"))
      (node (ref "Q1") (pin "6") (pinfunction "DRAIN_6") (pintype "passive"))
      (node (ref "Q1") (pin "7") (pinfunction "DRAIN_7") (pintype "passive"))
      (node (ref "Q1") (pin "8") (pinfunction "DRAIN_8") (pintype "passive"))
      (node (ref "R2") (pin "2") (pinfunction "2_2") (pintype "passive"))
      (node (ref "U6") (pin "1") (pinfunction "IN-_1") (pintype "passive"))
    )
    (net (code "17") (name "/C2P") (class "Default")
      (node (ref "C11") (pin "1") (pinfunction "1_1") (pintype "passive"))
      (node (ref "C3") (pin "1") (pinfunction "1_1") (pintype "passive"))
      (node (ref "C4") (pin "1") (pinfunction "1_1") (pintype "passive"))
      (node (ref "C7") (pin "1") (pinfunction "1_1") (pintype "passive"))
      (node (ref "C8") (pin "1") (pinfunction "1_1") (pintype "passive"))
      (node (ref "Q2") (pin "5") (pinfunction "DRAIN_5") (pintype "passive"))
      (node (ref "Q2") (pin "6") (pinfunction "DRAIN_6") (pintype "passive"))
      (node (ref "Q2") (pin "7") (pinfunction "DRAIN_7") (pintype "passive"))
      (node (ref "Q2") (pin "8") (pinfunction "DRAIN_8") (pintype "passive"))
      (node (ref "R4") (pin "1") (pinfunction "1_1") (pintype "passive"))
      (node (ref "U7") (pin "8") (pinfunction "IN+_8") (pintype "passive"))
    )
    (net (code "18") (name "/CANH") (class "Default")
      (node (ref "CN6") (pin "1") (pinfunction "1_1") (pintype "passive"))
      (node (ref "CN7") (pin "1") (pinfunction "1_1") (pintype "passive"))
      (node (ref "CN8") (pin "1") (pinfunction "1_1") (pintype "passive"))
      (node (ref "SW1") (pin "2") (pinfunction "2_2") (pintype "passive"))
      (node (ref "U1") (pin "7") (pinfunction "CANH_7") (pintype "passive"))
    )
    (net (code "19") (name "/CANL") (class "Default")
      (node (ref "CN6") (pin "2") (pinfunction "2_2") (pintype "passive"))
      (node (ref "CN7") (pin "2") (pinfunction "2_2") (pintype "passive"))
      (node (ref "CN8") (pin "2") (pinfunction "2_2") (pintype "passive"))
      (node (ref "R18") (pin "1") (pinfunction "1_1") (pintype "passive"))
      (node (ref "U1") (pin "6") (pinfunction "CANL_6") (pintype "passive"))
    )
    (net (code "20") (name "/CAN_RX") (class "Default")
      (node (ref "R10") (pin "1") (pinfunction "1_1") (pintype "passive"))
      (node (ref "U1") (pin "4") (pinfunction "R_4") (pintype "passive"))
    )
    (net (code "21") (name "/CAN_TX") (class "Default")
      (node (ref "R9") (pin "1") (pinfunction "1_1") (pintype "passive"))
      (node (ref "U1") (pin "1") (pinfunction "D_1") (pintype "passive"))
    )
    (net (code "22") (name "/CS") (class "Default")
      (node (ref "Screen1") (pin "8") (pinfunction "8_8") (pintype "passive"))
      (node (ref "U8") (pin "51") (pinfunction "PB12_51") (pintype "passive"))
    )
    (net (code "23") (name "/ENA") (class "Default")
      (node (ref "R25") (pin "2") (pinfunction "2_2") (pintype "passive"))
      (node (ref "R26") (pin "2") (pinfunction "2_2") (pintype "passive"))
      (node (ref "U2") (pin "2") (pinfunction "~{SD}_2") (pintype "input"))
    )
    (net (code "24") (name "/ENB") (class "Default")
      (node (ref "R23") (pin "2") (pinfunction "2_2") (pintype "passive"))
      (node (ref "R27") (pin "2") (pinfunction "2_2") (pintype "passive"))
      (node (ref "U3") (pin "2") (pinfunction "~{SD}_2") (pintype "input"))
    )
    (net (code "25") (name "/IL+") (class "Default")
      (node (ref "L1") (pin "2") (pinfunction "2_2") (pintype "passive"))
      (node (ref "R3") (pin "1") (pinfunction "1_1") (pintype "passive"))
      (node (ref "U4") (pin "8") (pinfunction "IN+_8") (pintype "passive"))
    )
    (net (code "26") (name "/Key1") (class "Default")
      (node (ref "K1") (pin "3") (pinfunction "3_3") (pintype "passive"))
      (node (ref "R5") (pin "1") (pinfunction "1_1") (pintype "passive"))
      (node (ref "U8") (pin "63") (pinfunction "PC6_63") (pintype "passive"))
    )
    (net (code "27") (name "/Key2") (class "Default")
      (node (ref "K2") (pin "3") (pinfunction "3_3") (pintype "passive"))
      (node (ref "R6") (pin "1") (pinfunction "1_1") (pintype "passive"))
      (node (ref "U8") (pin "64") (pinfunction "PC7_64") (pintype "passive"))
    )
    (net (code "28") (name "/Key3") (class "Default")
      (node (ref "K3") (pin "3") (pinfunction "3_3") (pintype "passive"))
      (node (ref "R7") (pin "1") (pinfunction "1_1") (pintype "passive"))
      (node (ref "U8") (pin "65") (pinfunction "PC8_65") (pintype "passive"))
    )
    (net (code "29") (name "/LEDB-") (class "Default")
      (node (ref "LED1") (pin "1") (pinfunction "B-_1") (pintype "passive"))
      (node (ref "U8") (pin "62") (pinfunction "PD15_62") (pintype "passive"))
    )
    (net (code "30") (name "/LEDG-") (class "Default")
      (node (ref "LED1") (pin "5") (pinfunction "G-_5") (pintype "passive"))
      (node (ref "U8") (pin "60") (pinfunction "PD13_60") (pintype "passive"))
    )
    (net (code "31") (name "/LEDR-") (class "Default")
      (node (ref "LED1") (pin "3") (pinfunction "R-_3") (pintype "passive"))
      (node (ref "U8") (pin "61") (pinfunction "PD14_61") (pintype "passive"))
    )
    (net (code "32") (name "/NRST") (class "Default")
      (node (ref "H1") (pin "1") (pinfunction "1_1") (pintype "passive"))
      (node (ref "K4") (pin "3") (pinfunction "3_3") (pintype "passive"))
      (node (ref "R37") (pin "1") (pinfunction "1_1") (pintype "passive"))
      (node (ref "U8") (pin "14") (pinfunction "NRST_14") (pintype "passive"))
    )
    (net (code "33") (name "/OSC_IN") (class "Default")
      (node (ref "C46") (pin "1") (pinfunction "1_1") (pintype "passive"))
      (node (ref "U8") (pin "12") (pinfunction "PH0-OSC_IN_12") (pintype "passive"))
      (node (ref "X1") (pin "3") (pinfunction "OUT_3") (pintype "passive"))
    )
    (net (code "34") (name "/PWMA") (class "Default")
      (node (ref "R28") (pin "2") (pinfunction "2_2") (pintype "passive"))
      (node (ref "U2") (pin "1") (pinfunction "IN_1") (pintype "input"))
    )
    (net (code "35") (name "/PWMB") (class "Default")
      (node (ref "R24") (pin "2") (pinfunction "2_2") (pintype "passive"))
      (node (ref "U3") (pin "1") (pinfunction "IN_1") (pintype "input"))
    )
    (net (code "36") (name "/RESET") (class "Default")
      (node (ref "Screen1") (pin "3") (pinfunction "3_3") (pintype "passive"))
      (node (ref "U8") (pin "56") (pinfunction "PD9_56") (pintype "passive"))
    )
    (net (code "37") (name "/RS") (class "Default")
      (node (ref "Screen1") (pin "4") (pinfunction "4_4") (pintype "passive"))
      (node (ref "U8") (pin "55") (pinfunction "PD8_55") (pintype "passive"))
    )
    (net (code "38") (name "/SCL") (class "Default")
      (node (ref "Screen1") (pin "6") (pinfunction "6_6") (pintype "passive"))
      (node (ref "U8") (pin "52") (pinfunction "PB13_52") (pintype "passive"))
    )
    (net (code "39") (name "/SDA") (class "Default")
      (node (ref "Screen1") (pin "5") (pinfunction "5_5") (pintype "passive"))
      (node (ref "U8") (pin "54") (pinfunction "PB15_54") (pintype "passive"))
    )
    (net (code "40") (name "/SWCLK") (class "Default")
      (node (ref "R35") (pin "1") (pinfunction "1_1") (pintype "passive"))
      (node (ref "R41") (pin "2") (pinfunction "2_2") (pintype "passive"))
      (node (ref "U8") (pin "76") (pinfunction "PA14_76") (pintype "passive"))
    )
    (net (code "41") (name "/SWDIO") (class "Default")
      (node (ref "R36") (pin "1") (pinfunction "1_1") (pintype "passive"))
      (node (ref "R40") (pin "2") (pinfunction "2_2") (pintype "passive"))
      (node (ref "U8") (pin "72") (pinfunction "PA13_72") (pintype "passive"))
    )
    (net (code "42") (name "/USART1_RX") (class "Default")
      (node (ref "H1") (pin "3") (pinfunction "3_3") (pintype "passive"))
      (node (ref "U8") (pin "69") (pinfunction "PA10_69") (pintype "passive"))
    )
    (net (code "43") (name "/USART1_TX") (class "Default")
      (node (ref "H1") (pin "2") (pinfunction "2_2") (pintype "passive"))
      (node (ref "U8") (pin "68") (pinfunction "PA9_68") (pintype "passive"))
    )
    (net (code "44") (name "/Vref+") (class "Default")
      (node (ref "C38") (pin "2") (pinfunction "2_2") (pintype "passive"))
      (node (ref "C47") (pin "1") (pinfunction "1_1") (pintype "passive"))
      (node (ref "C48") (pin "2") (pinfunction "2_2") (pintype "passive"))
      (node (ref "C49") (pin "2") (pinfunction "2_2") (pintype "passive"))
      (node (ref "C50") (pin "1") (pinfunction "1_1") (pintype "passive"))
      (node (ref "U4") (pin "3") (pinfunction "REF2_3") (pintype "passive"))
      (node (ref "U5") (pin "2") (pinfunction "OUT_2") (pintype "passive"))
      (node (ref "U6") (pin "3") (pinfunction "REF2_3") (pintype "passive"))
      (node (ref "U7") (pin "3") (pinfunction "REF2_3") (pintype "passive"))
      (node (ref "U8") (pin "20") (pinfunction "VREF+_20") (pintype "passive"))
    )
    (net (code "45") (name "AGND") (class "Default")
      (node (ref "C1") (pin "2") (pinfunction "2_2") (pintype "passive"))
      (node (ref "C11") (pin "2") (pinfunction "2_2") (pintype "passive"))
      (node (ref "C2") (pin "2") (pinfunction "2_2") (pintype "passive"))
      (node (ref "C21") (pin "2") (pinfunction "2_2") (pintype "passive"))
      (node (ref "C22") (pin "1") (pinfunction "1_1") (pintype "passive"))
      (node (ref "C23") (pin "1") (pinfunction "1_1") (pintype "passive"))
      (node (ref "C24") (pin "1") (pinfunction "1_1") (pintype "passive"))
      (node (ref "C27") (pin "1") (pinfunction "1_1") (pintype "passive"))
      (node (ref "C28") (pin "2") (pinfunction "2_2") (pintype "passive"))
      (node (ref "C29") (pin "2") (pinfunction "2_2") (pintype "passive"))
      (node (ref "C3") (pin "2") (pinfunction "2_2") (pintype "passive"))
      (node (ref "C30") (pin "1") (pinfunction "1_1") (pintype "passive"))
      (node (ref "C31") (pin "1") (pinfunction "1_1") (pintype "passive"))
      (node (ref "C32") (pin "1") (pinfunction "1_1") (pintype "passive"))
      (node (ref "C33") (pin "1") (pinfunction "1_1") (pintype "passive"))
      (node (ref "C34") (pin "1") (pinfunction "1_1") (pintype "passive"))
      (node (ref "C35") (pin "1") (pinfunction "1_1") (pintype "passive"))
      (node (ref "C36") (pin "1") (pinfunction "1_1") (pintype "passive"))
      (node (ref "C37") (pin "2") (pinfunction "2_2") (pintype "passive"))
      (node (ref "C38") (pin "1") (pinfunction "1_1") (pintype "passive"))
      (node (ref "C39") (pin "2") (pinfunction "2_2") (pintype "passive"))
      (node (ref "C4") (pin "2") (pinfunction "2_2") (pintype "passive"))
      (node (ref "C40") (pin "1") (pinfunction "1_1") (pintype "passive"))
      (node (ref "C41") (pin "1") (pinfunction "1_1") (pintype "passive"))
      (node (ref "C42") (pin "1") (pinfunction "1_1") (pintype "passive"))
      (node (ref "C43") (pin "1") (pinfunction "1_1") (pintype "passive"))
      (node (ref "C44") (pin "1") (pinfunction "1_1") (pintype "passive"))
      (node (ref "C45") (pin "1") (pinfunction "1_1") (pintype "passive"))
      (node (ref "C46") (pin "2") (pinfunction "2_2") (pintype "passive"))
      (node (ref "C47") (pin "2") (pinfunction "2_2") (pintype "passive"))
      (node (ref "C48") (pin "1") (pinfunction "1_1") (pintype "passive"))
      (node (ref "C49") (pin "1") (pinfunction "1_1") (pintype "passive"))
      (node (ref "C5") (pin "2") (pinfunction "2_2") (pintype "passive"))
      (node (ref "C50") (pin "2") (pinfunction "2_2") (pintype "passive"))
      (node (ref "C6") (pin "2") (pinfunction "2_2") (pintype "passive"))
      (node (ref "C7") (pin "2") (pinfunction "2_2") (pintype "passive"))
      (node (ref "C8") (pin "2") (pinfunction "2_2") (pintype "passive"))
      (node (ref "C9") (pin "2") (pinfunction "2_2") (pintype "passive"))
      (node (ref "CN3") (pin "2") (pinfunction "2_2") (pintype "passive"))
      (node (ref "CN4") (pin "1") (pinfunction "1_1") (pintype "passive"))
      (node (ref "CN4") (pin "2") (pinfunction "2_2") (pintype "passive"))
      (node (ref "CN5") (pin "1") (pinfunction "1_1") (pintype "passive"))
      (node (ref "CN5") (pin "2") (pinfunction "2_2") (pintype "passive"))
      (node (ref "H1") (pin "7") (pinfunction "7_7") (pintype "passive"))
      (node (ref "K1") (pin "1") (pinfunction "1_1") (pintype "passive"))
      (node (ref "K2") (pin "1") (pinfunction "1_1") (pintype "passive"))
      (node (ref "K3") (pin "1") (pinfunction "1_1") (pintype "passive"))
      (node (ref "K4") (pin "1") (pinfunction "1_1") (pintype "passive"))
      (node (ref "LED2") (pin "2") (pinfunction "K_2") (pintype "passive"))
      (node (ref "Q3") (pin "1") (pinfunction "SOURCE_1") (pintype "passive"))
      (node (ref "Q3") (pin "2") (pinfunction "SOURCE_2") (pintype "passive"))
      (node (ref "Q3") (pin "3") (pinfunction "SOURCE_3") (pintype "passive"))
      (node (ref "Q4") (pin "1") (pinfunction "SOURCE_1") (pintype "passive"))
      (node (ref "Q4") (pin "2") (pinfunction "SOURCE_2") (pintype "passive"))
      (node (ref "Q4") (pin "3") (pinfunction "SOURCE_3") (pintype "passive"))
      (node (ref "R14") (pin "1") (pinfunction "1_1") (pintype "passive"))
      (node (ref "R16") (pin "1") (pinfunction "1_1") (pintype "passive"))
      (node (ref "R17") (pin "1") (pinfunction "1_1") (pintype "passive"))
      (node (ref "R26") (pin "1") (pinfunction "1_1") (pintype "passive"))
      (node (ref "R27") (pin "1") (pinfunction "1_1") (pintype "passive"))
      (node (ref "R31") (pin "1") (pinfunction "1_1") (pintype "passive"))
      (node (ref "R32") (pin "2") (pinfunction "2_2") (pintype "passive"))
      (node (ref "R35") (pin "2") (pinfunction "2_2") (pintype "passive"))
      (node (ref "R38") (pin "1") (pinfunction "1_1") (pintype "passive"))
      (node (ref "R39") (pin "1") (pinfunction "1_1") (pintype "passive"))
      (node (ref "Screen1") (pin "2") (pinfunction "2_2") (pintype "passive"))
      (node (ref "U1") (pin "2") (pinfunction "GND_2") (pintype "passive"))
      (node (ref "U1") (pin "8") (pinfunction "RS_8") (pintype "passive"))
      (node (ref "U10") (pin "4") (pinfunction "VSS_4") (pintype "passive"))
      (node (ref "U11") (pin "1") (pinfunction "GND_1") (pintype "power_in"))
      (node (ref "U2") (pin "3") (pinfunction "COM_3") (pintype "power_in"))
      (node (ref "U3") (pin "3") (pinfunction "COM_3") (pintype "power_in"))
      (node (ref "U4") (pin "2") (pinfunction "GND_2") (pintype "passive"))
      (node (ref "U4") (pin "7") (pinfunction "REF1_7") (pintype "passive"))
      (node (ref "U5") (pin "3") (pinfunction "GND_3") (pintype "passive"))
      (node (ref "U6") (pin "2") (pinfunction "GND_2") (pintype "passive"))
      (node (ref "U6") (pin "7") (pinfunction "REF1_7") (pintype "passive"))
      (node (ref "U7") (pin "2") (pinfunction "GND_2") (pintype "passive"))
      (node (ref "U7") (pin "7") (pinfunction "REF1_7") (pintype "passive"))
      (node (ref "U8") (pin "10") (pinfunction "VSS_10") (pintype "passive"))
      (node (ref "U8") (pin "19") (pinfunction "VSSA_19") (pintype "passive"))
      (node (ref "U8") (pin "26") (pinfunction "VSS_26") (pintype "passive"))
      (node (ref "U8") (pin "49") (pinfunction "VSS_49") (pintype "passive"))
      (node (ref "U8") (pin "74") (pinfunction "VSS_74") (pintype "passive"))
      (node (ref "U8") (pin "99") (pinfunction "VSS_99") (pintype "passive"))
      (node (ref "U9") (pin "1") (pinfunction "GND_1") (pintype "power_in"))
      (node (ref "X1") (pin "2") (pinfunction "GND_2") (pintype "passive"))
    )
    (net (code "46") (name "Net-(C24-Pad2)") (class "Default")
      (node (ref "C24") (pin "2") (pinfunction "2_2") (pintype "passive"))
      (node (ref "U8") (pin "73") (pinfunction "VCAP_73") (pintype "passive"))
    )
    (net (code "47") (name "Net-(C29-Pad1)") (class "Default")
      (node (ref "C29") (pin "1") (pinfunction "1_1") (pintype "passive"))
      (node (ref "U8") (pin "48") (pinfunction "VCAP_48") (pintype "passive"))
    )
    (net (code "48") (name "Net-(D1-K)") (class "Default")
      (node (ref "D1") (pin "1") (pinfunction "K_1") (pintype "passive"))
      (node (ref "R19") (pin "1") (pinfunction "1_1") (pintype "passive"))
      (node (ref "U2") (pin "7") (pinfunction "HO_7") (pintype "output"))
    )
    (net (code "49") (name "Net-(D2-K)") (class "Default")
      (node (ref "D2") (pin "1") (pinfunction "K_1") (pintype "passive"))
      (node (ref "R20") (pin "1") (pinfunction "1_1") (pintype "passive"))
      (node (ref "U3") (pin "7") (pinfunction "HO_7") (pintype "output"))
    )
    (net (code "50") (name "Net-(D3-C)") (class "Default")
      (node (ref "C25") (pin "1") (pinfunction "1_1") (pintype "passive"))
      (node (ref "D3") (pin "2") (pinfunction "C_2") (pintype "passive"))
      (node (ref "U2") (pin "8") (pinfunction "VB_8") (pintype "power_in"))
    )
    (net (code "51") (name "Net-(D4-C)") (class "Default")
      (node (ref "C26") (pin "1") (pinfunction "1_1") (pintype "passive"))
      (node (ref "D4") (pin "2") (pinfunction "C_2") (pintype "passive"))
      (node (ref "U3") (pin "8") (pinfunction "VB_8") (pintype "power_in"))
    )
    (net (code "52") (name "Net-(D5-K)") (class "Default")
      (node (ref "D5") (pin "1") (pinfunction "K_1") (pintype "passive"))
      (node (ref "R21") (pin "1") (pinfunction "1_1") (pintype "passive"))
      (node (ref "U2") (pin "4") (pinfunction "LO_4") (pintype "output"))
    )
    (net (code "53") (name "Net-(D6-K)") (class "Default")
      (node (ref "D6") (pin "1") (pinfunction "K_1") (pintype "passive"))
      (node (ref "R22") (pin "1") (pinfunction "1_1") (pintype "passive"))
      (node (ref "U3") (pin "4") (pinfunction "LO_4") (pintype "output"))
    )
    (net (code "54") (name "Net-(H1-Pad4)") (class "Default")
      (node (ref "H1") (pin "4") (pinfunction "4_4") (pintype "passive"))
      (node (ref "R41") (pin "1") (pinfunction "1_1") (pintype "passive"))
    )
    (net (code "55") (name "Net-(H1-Pad5)") (class "Default")
      (node (ref "H1") (pin "5") (pinfunction "5_5") (pintype "passive"))
      (node (ref "R40") (pin "1") (pinfunction "1_1") (pintype "passive"))
    )
    (net (code "56") (name "Net-(LED1-B+)") (class "Default")
      (node (ref "LED1") (pin "2") (pinfunction "B+_2") (pintype "passive"))
      (node (ref "R1") (pin "1") (pinfunction "1_1") (pintype "passive"))
    )
    (net (code "57") (name "Net-(LED1-G+)") (class "Default")
      (node (ref "LED1") (pin "6") (pinfunction "G+_6") (pintype "passive"))
      (node (ref "R11") (pin "1") (pinfunction "1_1") (pintype "passive"))
    )
    (net (code "58") (name "Net-(LED1-R+)") (class "Default")
      (node (ref "LED1") (pin "4") (pinfunction "R+_4") (pintype "passive"))
      (node (ref "R8") (pin "1") (pinfunction "1_1") (pintype "passive"))
    )
    (net (code "59") (name "Net-(LED2-A)") (class "Default")
      (node (ref "LED2") (pin "1") (pinfunction "A_1") (pintype "passive"))
      (node (ref "R15") (pin "2") (pinfunction "2_2") (pintype "passive"))
    )
    (net (code "60") (name "Net-(R18-Pad2)") (class "Default")
      (node (ref "R18") (pin "2") (pinfunction "2_2") (pintype "passive"))
      (node (ref "SW1") (pin "1") (pinfunction "1_1") (pintype "passive"))
    )
    (net (code "61") (name "Net-(U8-BOOT0)") (class "Default")
      (node (ref "R14") (pin "2") (pinfunction "2_2") (pintype "passive"))
      (node (ref "U8") (pin "94") (pinfunction "BOOT0_94") (pintype "passive"))
    )
    (net (code "62") (name "Net-(U8-PB8)") (class "Default")
      (node (ref "R10") (pin "2") (pinfunction "2_2") (pintype "passive"))
      (node (ref "U8") (pin "95") (pinfunction "PB8_95") (pintype "passive"))
    )
    (net (code "63") (name "Net-(U8-PB9)") (class "Default")
      (node (ref "R9") (pin "2") (pinfunction "2_2") (pintype "passive"))
      (node (ref "U8") (pin "96") (pinfunction "PB9_96") (pintype "passive"))
    )
    (net (code "64") (name "Net-(U8-PE8)") (class "Default")
      (node (ref "R23") (pin "1") (pinfunction "1_1") (pintype "passive"))
      (node (ref "U8") (pin "38") (pinfunction "PE8_38") (pintype "passive"))
    )
    (net (code "65") (name "Net-(U8-PE9)") (class "Default")
      (node (ref "R24") (pin "1") (pinfunction "1_1") (pintype "passive"))
      (node (ref "U8") (pin "39") (pinfunction "PE9_39") (pintype "passive"))
    )
    (net (code "66") (name "Net-(U8-PE10)") (class "Default")
      (node (ref "R25") (pin "1") (pinfunction "1_1") (pintype "passive"))
      (node (ref "U8") (pin "40") (pinfunction "PE10_40") (pintype "passive"))
    )
    (net (code "67") (name "Net-(U8-PE11)") (class "Default")
      (node (ref "R28") (pin "1") (pinfunction "1_1") (pintype "passive"))
      (node (ref "U8") (pin "41") (pinfunction "PE11_41") (pintype "passive"))
    )
    (net (code "68") (name "Net-(U10-INA+)") (class "Default")
      (node (ref "R33") (pin "2") (pinfunction "2_2") (pintype "passive"))
      (node (ref "R38") (pin "2") (pinfunction "2_2") (pintype "passive"))
      (node (ref "U10") (pin "3") (pinfunction "INA+_3") (pintype "passive"))
    )
    (net (code "69") (name "Net-(U10-INA-)") (class "Default")
      (node (ref "R29") (pin "1") (pinfunction "1_1") (pintype "passive"))
      (node (ref "R31") (pin "2") (pinfunction "2_2") (pintype "passive"))
      (node (ref "U10") (pin "2") (pinfunction "INA-_2") (pintype "passive"))
    )
    (net (code "70") (name "Net-(U10-INB+)") (class "Default")
      (node (ref "R34") (pin "1") (pinfunction "1_1") (pintype "passive"))
      (node (ref "R39") (pin "2") (pinfunction "2_2") (pintype "passive"))
      (node (ref "U10") (pin "5") (pinfunction "INB+_5") (pintype "passive"))
    )
    (net (code "71") (name "Net-(U10-INB-)") (class "Default")
      (node (ref "R30") (pin "1") (pinfunction "1_1") (pintype "passive"))
      (node (ref "R32") (pin "1") (pinfunction "1_1") (pintype "passive"))
      (node (ref "U10") (pin "6") (pinfunction "INB-_6") (pintype "passive"))
    )
    (net (code "72") (name "VM1+") (class "Default")
      (node (ref "CN1") (pin "1") (pinfunction "1_1") (pintype "passive"))
      (node (ref "CN1") (pin "2") (pinfunction "2_2") (pintype "passive"))
      (node (ref "R2") (pin "1") (pinfunction "1_1") (pintype "passive"))
      (node (ref "R33") (pin "1") (pinfunction "1_1") (pintype "passive"))
      (node (ref "U6") (pin "8") (pinfunction "IN+_8") (pintype "passive"))
    )
    (net (code "73") (name "VM2+") (class "Default")
      (node (ref "CN2") (pin "1") (pinfunction "1_1") (pintype "passive"))
      (node (ref "CN2") (pin "2") (pinfunction "2_2") (pintype "passive"))
      (node (ref "R34") (pin "2") (pinfunction "2_2") (pintype "passive"))
      (node (ref "R4") (pin "2") (pinfunction "2_2") (pintype "passive"))
      (node (ref "U7") (pin "1") (pinfunction "IN-_1") (pintype "passive"))
    )
    (net (code "74") (name "unconnected-(CN6-Pad3)") (class "Default")
      (node (ref "CN6") (pin "3") (pinfunction "3_3") (pintype "passive+no_connect"))
    )
    (net (code "75") (name "unconnected-(CN6-Pad4)") (class "Default")
      (node (ref "CN6") (pin "4") (pinfunction "4_4") (pintype "passive+no_connect"))
    )
    (net (code "76") (name "unconnected-(CN7-Pad3)") (class "Default")
      (node (ref "CN7") (pin "3") (pinfunction "3_3") (pintype "passive+no_connect"))
    )
    (net (code "77") (name "unconnected-(CN7-Pad4)") (class "Default")
      (node (ref "CN7") (pin "4") (pinfunction "4_4") (pintype "passive+no_connect"))
    )
    (net (code "78") (name "unconnected-(CN8-Pad3)") (class "Default")
      (node (ref "CN8") (pin "3") (pinfunction "3_3") (pintype "passive+no_connect"))
    )
    (net (code "79") (name "unconnected-(CN8-Pad4)") (class "Default")
      (node (ref "CN8") (pin "4") (pinfunction "4_4") (pintype "passive+no_connect"))
    )
    (net (code "80") (name "unconnected-(K1-Pad2)") (class "Default")
      (node (ref "K1") (pin "2") (pinfunction "2_2") (pintype "passive+no_connect"))
    )
    (net (code "81") (name "unconnected-(K1-Pad4)") (class "Default")
      (node (ref "K1") (pin "4") (pinfunction "4_4") (pintype "passive+no_connect"))
    )
    (net (code "82") (name "unconnected-(K2-Pad2)") (class "Default")
      (node (ref "K2") (pin "2") (pinfunction "2_2") (pintype "passive+no_connect"))
    )
    (net (code "83") (name "unconnected-(K2-Pad4)") (class "Default")
      (node (ref "K2") (pin "4") (pinfunction "4_4") (pintype "passive+no_connect"))
    )
    (net (code "84") (name "unconnected-(K3-Pad2)") (class "Default")
      (node (ref "K3") (pin "2") (pinfunction "2_2") (pintype "passive+no_connect"))
    )
    (net (code "85") (name "unconnected-(K3-Pad4)") (class "Default")
      (node (ref "K3") (pin "4") (pinfunction "4_4") (pintype "passive+no_connect"))
    )
    (net (code "86") (name "unconnected-(K4-Pad2)") (class "Default")
      (node (ref "K4") (pin "2") (pinfunction "2_2") (pintype "passive+no_connect"))
    )
    (net (code "87") (name "unconnected-(K4-Pad4)") (class "Default")
      (node (ref "K4") (pin "4") (pinfunction "4_4") (pintype "passive+no_connect"))
    )
    (net (code "88") (name "unconnected-(M1-Pad1)") (class "Default")
      (node (ref "M1") (pin "1") (pinfunction "1_1") (pintype "passive+no_connect"))
    )
    (net (code "89") (name "unconnected-(M2-Pad1)") (class "Default")
      (node (ref "M2") (pin "1") (pinfunction "1_1") (pintype "passive+no_connect"))
    )
    (net (code "90") (name "unconnected-(M3-Pad1)") (class "Default")
      (node (ref "M3") (pin "1") (pinfunction "1_1") (pintype "passive+no_connect"))
    )
    (net (code "91") (name "unconnected-(M4-Pad1)") (class "Default")
      (node (ref "M4") (pin "1") (pinfunction "1_1") (pintype "passive+no_connect"))
    )
    (net (code "92") (name "unconnected-(U1-VREF-Pad5)") (class "Default")
      (node (ref "U1") (pin "5") (pinfunction "VREF_5") (pintype "passive+no_connect"))
    )
    (net (code "93") (name "unconnected-(U4-NC-Pad4)") (class "Default")
      (node (ref "U4") (pin "4") (pinfunction "NC_4") (pintype "passive+no_connect"))
    )
    (net (code "94") (name "unconnected-(U6-NC-Pad4)") (class "Default")
      (node (ref "U6") (pin "4") (pinfunction "NC_4") (pintype "passive+no_connect"))
    )
    (net (code "95") (name "unconnected-(U7-NC-Pad4)") (class "Default")
      (node (ref "U7") (pin "4") (pinfunction "NC_4") (pintype "passive+no_connect"))
    )
    (net (code "96") (name "unconnected-(U8-PA0-Pad22)") (class "Default")
      (node (ref "U8") (pin "22") (pinfunction "PA0_22") (pintype "passive+no_connect"))
    )
    (net (code "97") (name "unconnected-(U8-PA1-Pad23)") (class "Default")
      (node (ref "U8") (pin "23") (pinfunction "PA1_23") (pintype "passive+no_connect"))
    )
    (net (code "98") (name "unconnected-(U8-PA4-Pad28)") (class "Default")
      (node (ref "U8") (pin "28") (pinfunction "PA4_28") (pintype "passive+no_connect"))
    )
    (net (code "99") (name "unconnected-(U8-PA5-Pad29)") (class "Default")
      (node (ref "U8") (pin "29") (pinfunction "PA5_29") (pintype "passive+no_connect"))
    )
    (net (code "100") (name "unconnected-(U8-PA6-Pad30)") (class "Default")
      (node (ref "U8") (pin "30") (pinfunction "PA6_30") (pintype "passive+no_connect"))
    )
    (net (code "101") (name "unconnected-(U8-PA7-Pad31)") (class "Default")
      (node (ref "U8") (pin "31") (pinfunction "PA7_31") (pintype "passive+no_connect"))
    )
    (net (code "102") (name "unconnected-(U8-PA8-Pad67)") (class "Default")
      (node (ref "U8") (pin "67") (pinfunction "PA8_67") (pintype "passive+no_connect"))
    )
    (net (code "103") (name "unconnected-(U8-PA11-Pad70)") (class "Default")
      (node (ref "U8") (pin "70") (pinfunction "PA11_70") (pintype "passive+no_connect"))
    )
    (net (code "104") (name "unconnected-(U8-PA12-Pad71)") (class "Default")
      (node (ref "U8") (pin "71") (pinfunction "PA12_71") (pintype "passive+no_connect"))
    )
    (net (code "105") (name "unconnected-(U8-PA15-Pad77)") (class "Default")
      (node (ref "U8") (pin "77") (pinfunction "PA15_77") (pintype "passive+no_connect"))
    )
    (net (code "106") (name "unconnected-(U8-PB0-Pad34)") (class "Default")
      (node (ref "U8") (pin "34") (pinfunction "PB0_34") (pintype "passive+no_connect"))
    )
    (net (code "107") (name "unconnected-(U8-PB1-Pad35)") (class "Default")
      (node (ref "U8") (pin "35") (pinfunction "PB1_35") (pintype "passive+no_connect"))
    )
    (net (code "108") (name "unconnected-(U8-PB2-Pad36)") (class "Default")
      (node (ref "U8") (pin "36") (pinfunction "PB2_36") (pintype "passive+no_connect"))
    )
    (net (code "109") (name "unconnected-(U8-PB3-Pad89)") (class "Default")
      (node (ref "U8") (pin "89") (pinfunction "PB3_89") (pintype "passive+no_connect"))
    )
    (net (code "110") (name "unconnected-(U8-PB4-Pad90)") (class "Default")
      (node (ref "U8") (pin "90") (pinfunction "PB4_90") (pintype "passive+no_connect"))
    )
    (net (code "111") (name "unconnected-(U8-PB5-Pad91)") (class "Default")
      (node (ref "U8") (pin "91") (pinfunction "PB5_91") (pintype "passive+no_connect"))
    )
    (net (code "112") (name "unconnected-(U8-PB6-Pad92)") (class "Default")
      (node (ref "U8") (pin "92") (pinfunction "PB6_92") (pintype "passive+no_connect"))
    )
    (net (code "113") (name "unconnected-(U8-PB7-Pad93)") (class "Default")
      (node (ref "U8") (pin "93") (pinfunction "PB7_93") (pintype "passive+no_connect"))
    )
    (net (code "114") (name "unconnected-(U8-PB10-Pad46)") (class "Default")
      (node (ref "U8") (pin "46") (pinfunction "PB10_46") (pintype "passive+no_connect"))
    )
    (net (code "115") (name "unconnected-(U8-PB11-Pad47)") (class "Default")
      (node (ref "U8") (pin "47") (pinfunction "PB11_47") (pintype "passive+no_connect"))
    )
    (net (code "116") (name "unconnected-(U8-PB14-Pad53)") (class "Default")
      (node (ref "U8") (pin "53") (pinfunction "PB14_53") (pintype "passive+no_connect"))
    )
    (net (code "117") (name "unconnected-(U8-PC2_C-Pad17)") (class "Default")
      (node (ref "U8") (pin "17") (pinfunction "PC2_C_17") (pintype "passive+no_connect"))
    )
    (net (code "118") (name "unconnected-(U8-PC4-Pad32)") (class "Default")
      (node (ref "U8") (pin "32") (pinfunction "PC4_32") (pintype "passive+no_connect"))
    )
    (net (code "119") (name "unconnected-(U8-PC5-Pad33)") (class "Default")
      (node (ref "U8") (pin "33") (pinfunction "PC5_33") (pintype "passive+no_connect"))
    )
    (net (code "120") (name "unconnected-(U8-PC9-Pad66)") (class "Default")
      (node (ref "U8") (pin "66") (pinfunction "PC9_66") (pintype "passive+no_connect"))
    )
    (net (code "121") (name "unconnected-(U8-PC10-Pad78)") (class "Default")
      (node (ref "U8") (pin "78") (pinfunction "PC10_78") (pintype "passive+no_connect"))
    )
    (net (code "122") (name "unconnected-(U8-PC11-Pad79)") (class "Default")
      (node (ref "U8") (pin "79") (pinfunction "PC11_79") (pintype "passive+no_connect"))
    )
    (net (code "123") (name "unconnected-(U8-PC12-Pad80)") (class "Default")
      (node (ref "U8") (pin "80") (pinfunction "PC12_80") (pintype "passive+no_connect"))
    )
    (net (code "124") (name "unconnected-(U8-PC13-Pad7)") (class "Default")
      (node (ref "U8") (pin "7") (pinfunction "PC13_7") (pintype "passive+no_connect"))
    )
    (net (code "125") (name "unconnected-(U8-PC14-OSC32_IN-Pad8)") (class "Default")
      (node (ref "U8") (pin "8") (pinfunction "PC14-OSC32_IN_8") (pintype "passive+no_connect"))
    )
    (net (code "126") (name "unconnected-(U8-PC15-OSC32_OUT-Pad9)") (class "Default")
      (node (ref "U8") (pin "9") (pinfunction "PC15-OSC32_OUT_9") (pintype "passive+no_connect"))
    )
    (net (code "127") (name "unconnected-(U8-PD0-Pad81)") (class "Default")
      (node (ref "U8") (pin "81") (pinfunction "PD0_81") (pintype "passive+no_connect"))
    )
    (net (code "128") (name "unconnected-(U8-PD1-Pad82)") (class "Default")
      (node (ref "U8") (pin "82") (pinfunction "PD1_82") (pintype "passive+no_connect"))
    )
    (net (code "129") (name "unconnected-(U8-PD2-Pad83)") (class "Default")
      (node (ref "U8") (pin "83") (pinfunction "PD2_83") (pintype "passive+no_connect"))
    )
    (net (code "130") (name "unconnected-(U8-PD3-Pad84)") (class "Default")
      (node (ref "U8") (pin "84") (pinfunction "PD3_84") (pintype "passive+no_connect"))
    )
    (net (code "131") (name "unconnected-(U8-PD4-Pad85)") (class "Default")
      (node (ref "U8") (pin "85") (pinfunction "PD4_85") (pintype "passive+no_connect"))
    )
    (net (code "132") (name "unconnected-(U8-PD5-Pad86)") (class "Default")
      (node (ref "U8") (pin "86") (pinfunction "PD5_86") (pintype "passive+no_connect"))
    )
    (net (code "133") (name "unconnected-(U8-PD6-Pad87)") (class "Default")
      (node (ref "U8") (pin "87") (pinfunction "PD6_87") (pintype "passive+no_connect"))
    )
    (net (code "134") (name "unconnected-(U8-PD7-Pad88)") (class "Default")
      (node (ref "U8") (pin "88") (pinfunction "PD7_88") (pintype "passive+no_connect"))
    )
    (net (code "135") (name "unconnected-(U8-PD10-Pad57)") (class "Default")
      (node (ref "U8") (pin "57") (pinfunction "PD10_57") (pintype "passive+no_connect"))
    )
    (net (code "136") (name "unconnected-(U8-PD11-Pad58)") (class "Default")
      (node (ref "U8") (pin "58") (pinfunction "PD11_58") (pintype "passive+no_connect"))
    )
    (net (code "137") (name "unconnected-(U8-PE0-Pad97)") (class "Default")
      (node (ref "U8") (pin "97") (pinfunction "PE0_97") (pintype "passive+no_connect"))
    )
    (net (code "138") (name "unconnected-(U8-PE1-Pad98)") (class "Default")
      (node (ref "U8") (pin "98") (pinfunction "PE1_98") (pintype "passive+no_connect"))
    )
    (net (code "139") (name "unconnected-(U8-PE2-Pad1)") (class "Default")
      (node (ref "U8") (pin "1") (pinfunction "PE2_1") (pintype "passive+no_connect"))
    )
    (net (code "140") (name "unconnected-(U8-PE3-Pad2)") (class "Default")
      (node (ref "U8") (pin "2") (pinfunction "PE3_2") (pintype "passive+no_connect"))
    )
    (net (code "141") (name "unconnected-(U8-PE4-Pad3)") (class "Default")
      (node (ref "U8") (pin "3") (pinfunction "PE4_3") (pintype "passive+no_connect"))
    )
    (net (code "142") (name "unconnected-(U8-PE5-Pad4)") (class "Default")
      (node (ref "U8") (pin "4") (pinfunction "PE5_4") (pintype "passive+no_connect"))
    )
    (net (code "143") (name "unconnected-(U8-PE6-Pad5)") (class "Default")
      (node (ref "U8") (pin "5") (pinfunction "PE6_5") (pintype "passive+no_connect"))
    )
    (net (code "144") (name "unconnected-(U8-PE7-Pad37)") (class "Default")
      (node (ref "U8") (pin "37") (pinfunction "PE7_37") (pintype "passive+no_connect"))
    )
    (net (code "145") (name "unconnected-(U8-PE12-Pad42)") (class "Default")
      (node (ref "U8") (pin "42") (pinfunction "PE12_42") (pintype "passive+no_connect"))
    )
    (net (code "146") (name "unconnected-(U8-PE13-Pad43)") (class "Default")
      (node (ref "U8") (pin "43") (pinfunction "PE13_43") (pintype "passive+no_connect"))
    )
    (net (code "147") (name "unconnected-(U8-PE14-Pad44)") (class "Default")
      (node (ref "U8") (pin "44") (pinfunction "PE14_44") (pintype "passive+no_connect"))
    )
    (net (code "148") (name "unconnected-(U8-PE15-Pad45)") (class "Default")
      (node (ref "U8") (pin "45") (pinfunction "PE15_45") (pintype "passive+no_connect"))
    )
    (net (code "149") (name "unconnected-(U8-PH1-OSC_OUT-Pad13)") (class "Default")
      (node (ref "U8") (pin "13") (pinfunction "PH1-OSC_OUT_13") (pintype "passive+no_connect"))
    )
    (net (code "150") (name "unconnected-(X1-TRL-Pad1)") (class "Default")
      (node (ref "X1") (pin "1") (pinfunction "TRL_1") (pintype "passive+no_connect"))
    )
  )
)
